# plaits_5u_rev2.net
KiCad netlist of a schematic drawn in EAGLE
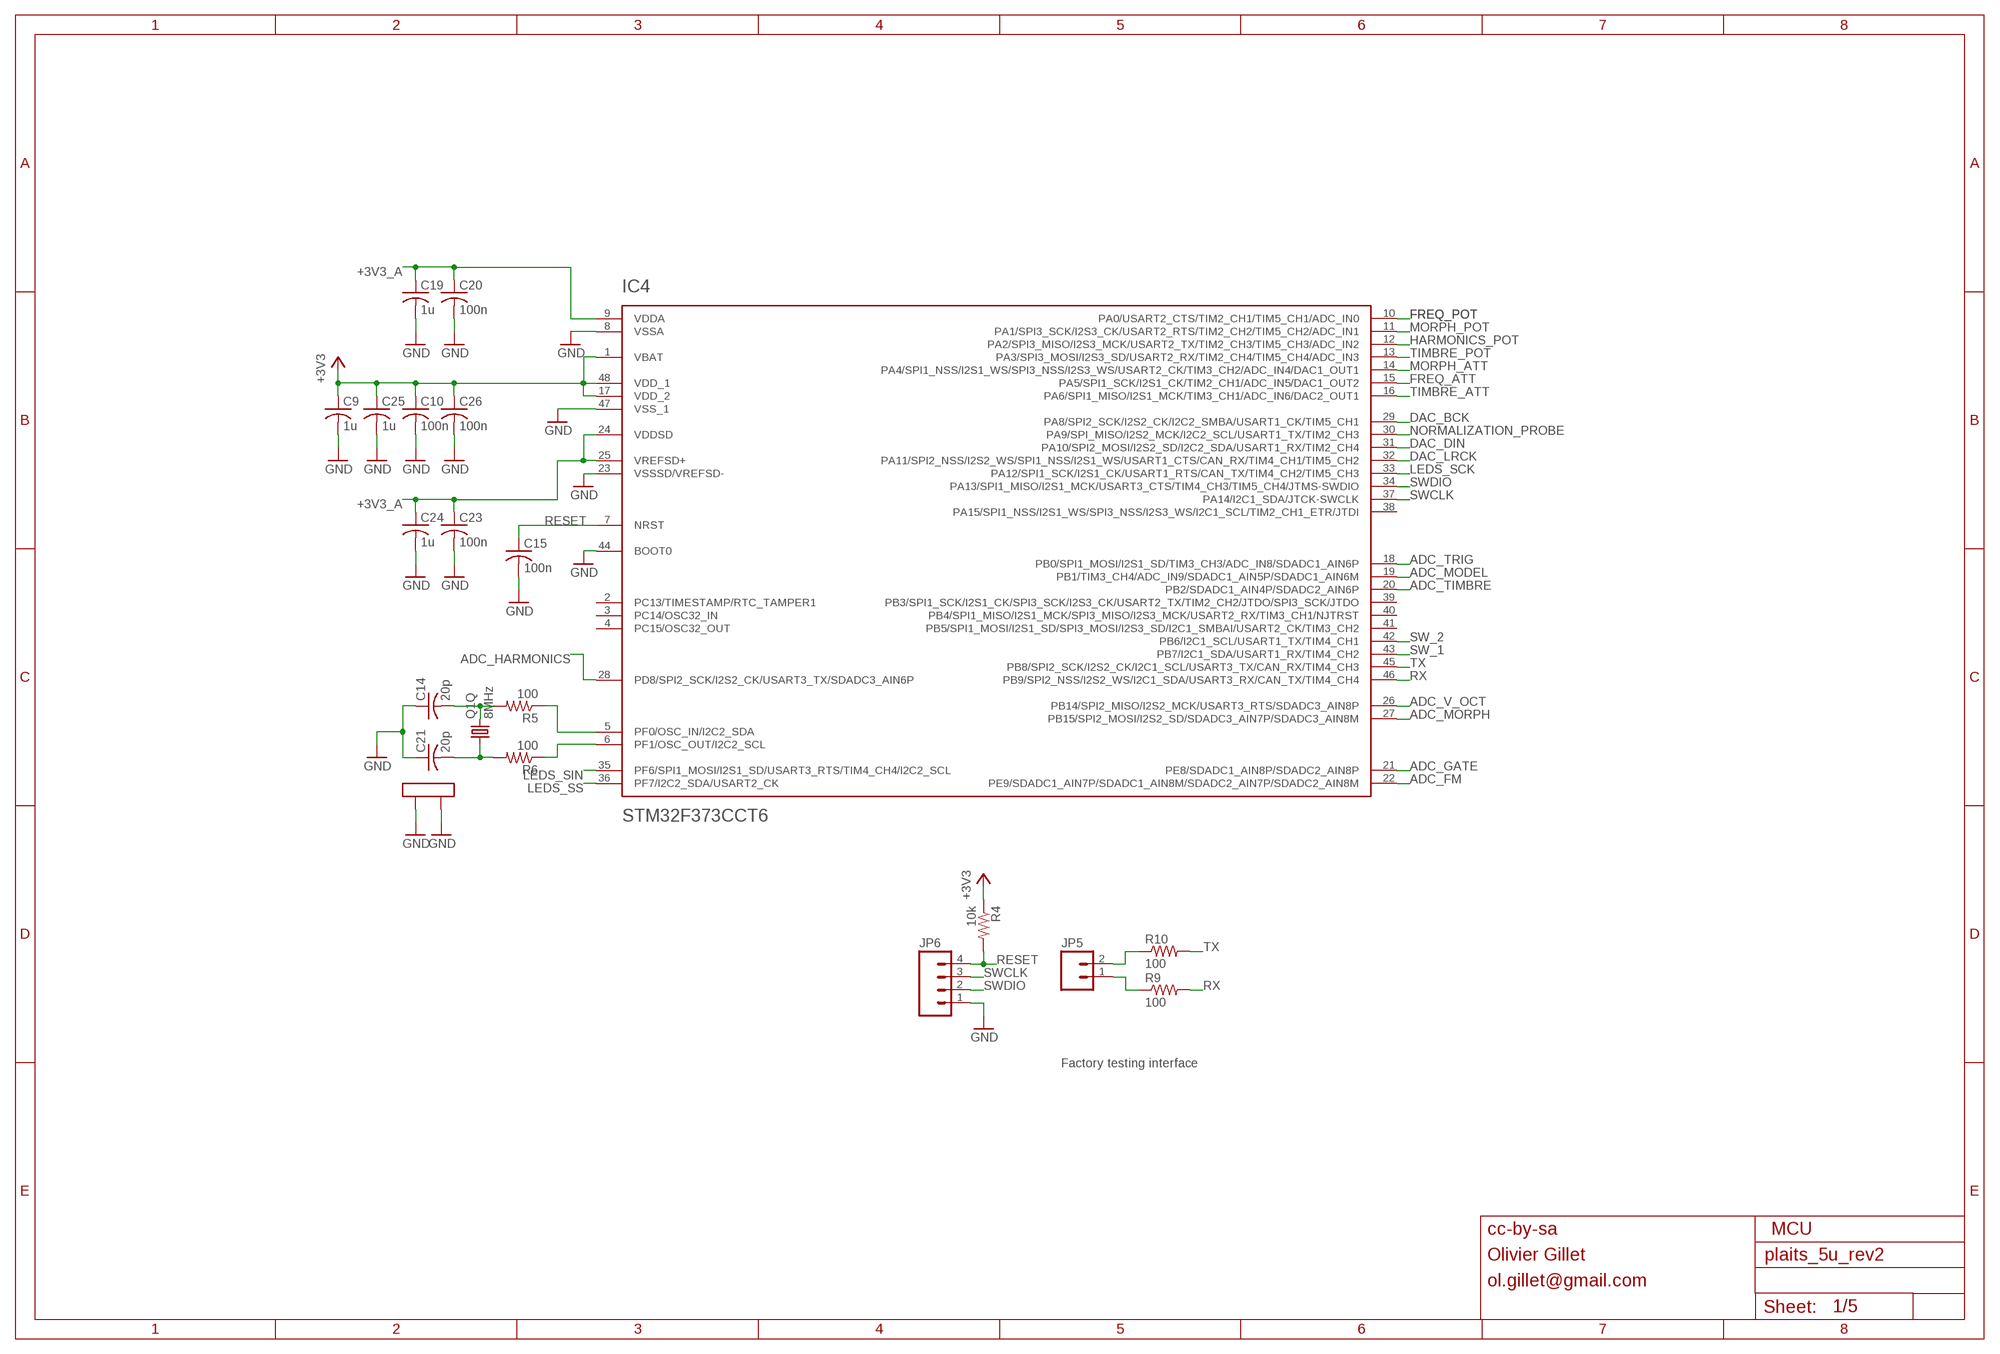
[diagram p0: schematic, sheet 1]
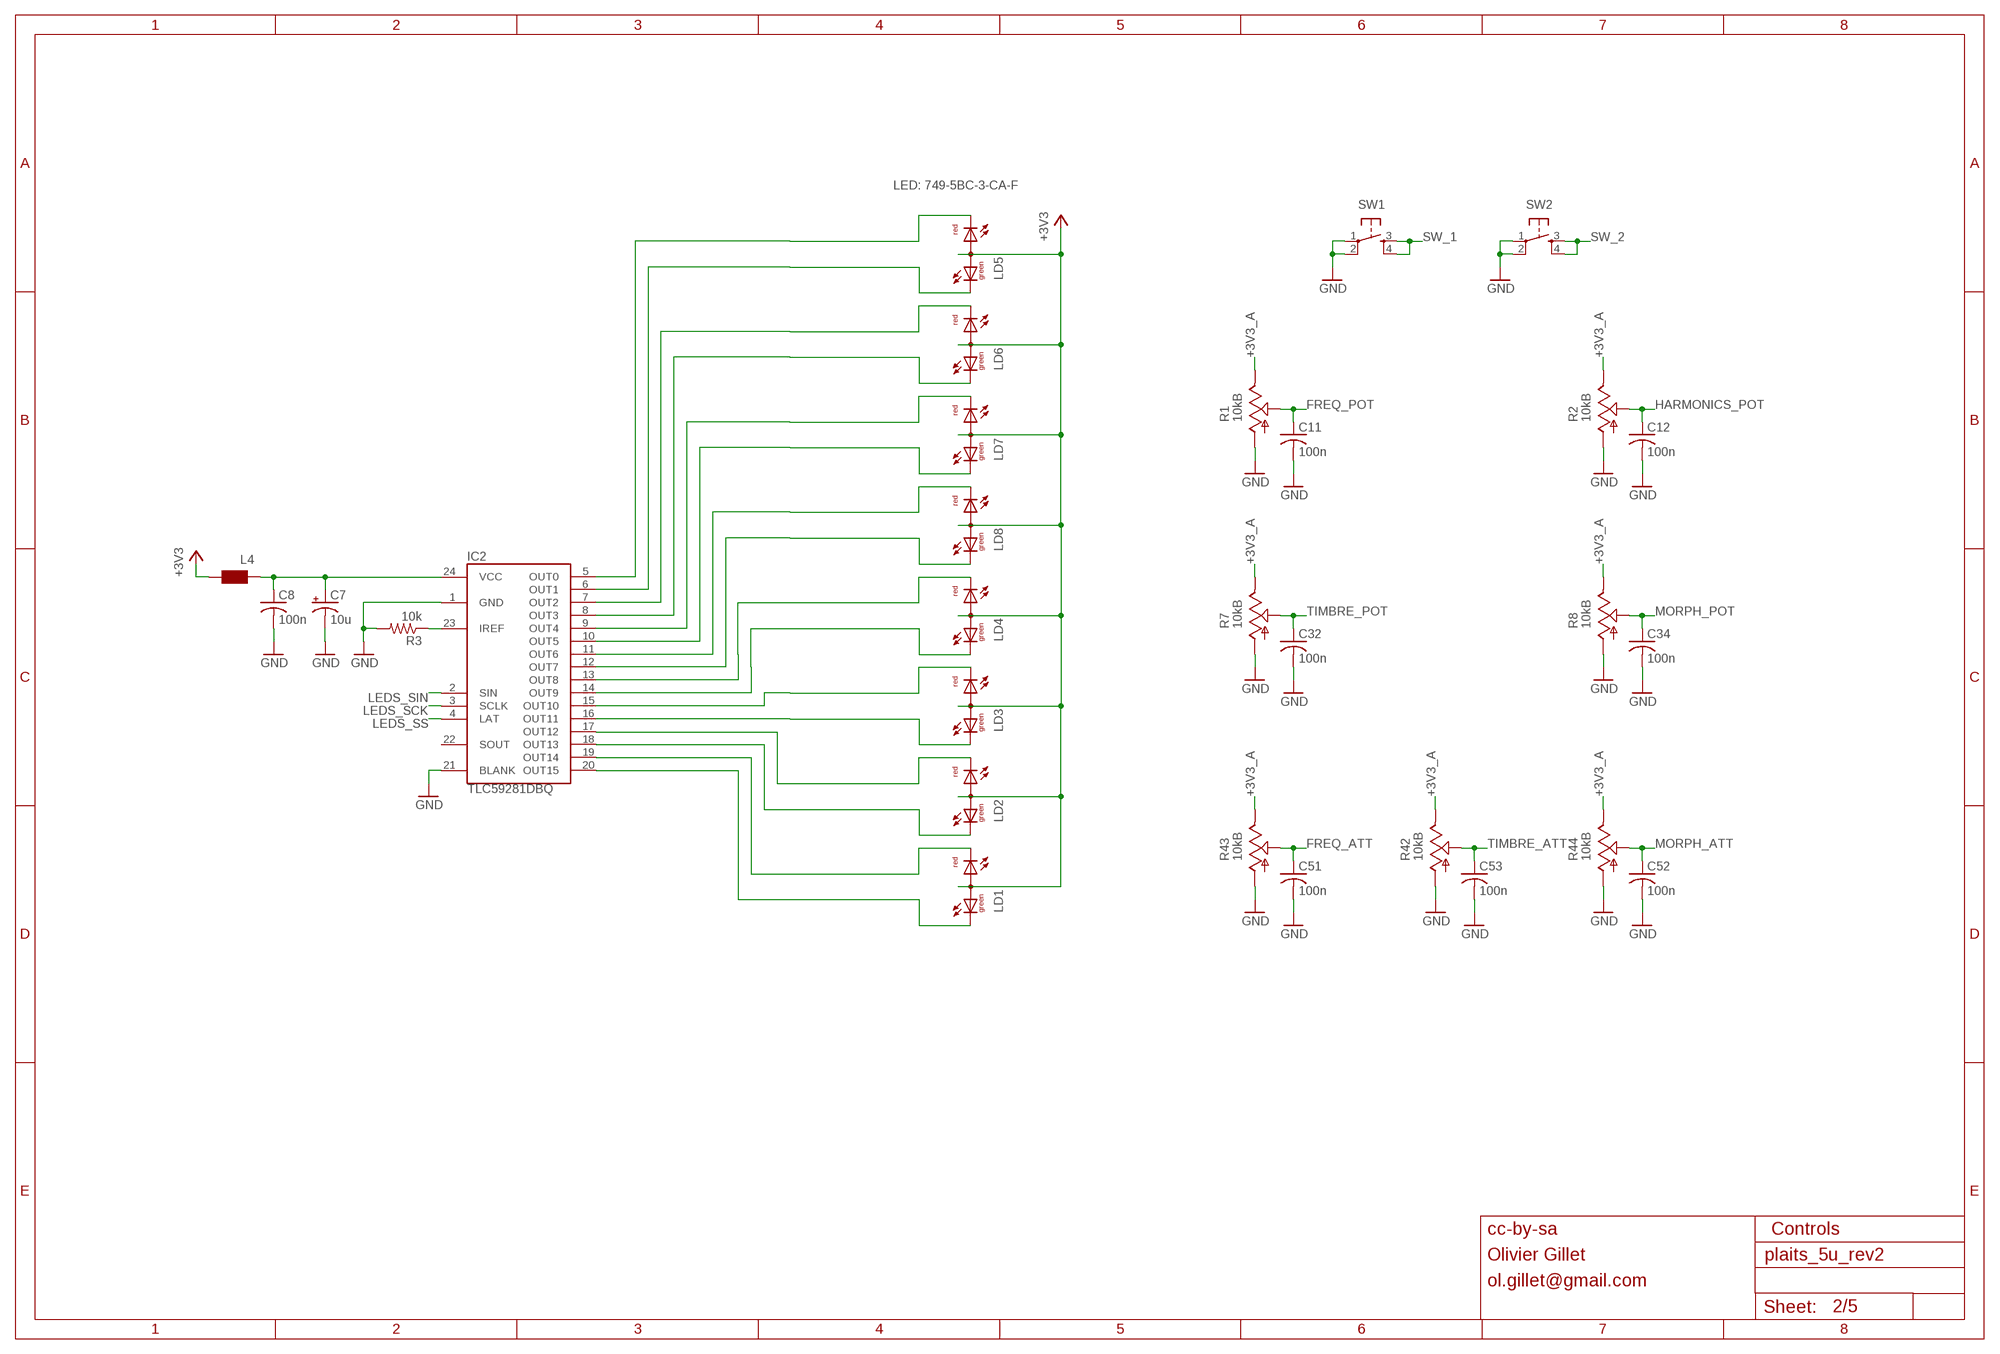
[diagram p1: schematic, sheet 2]
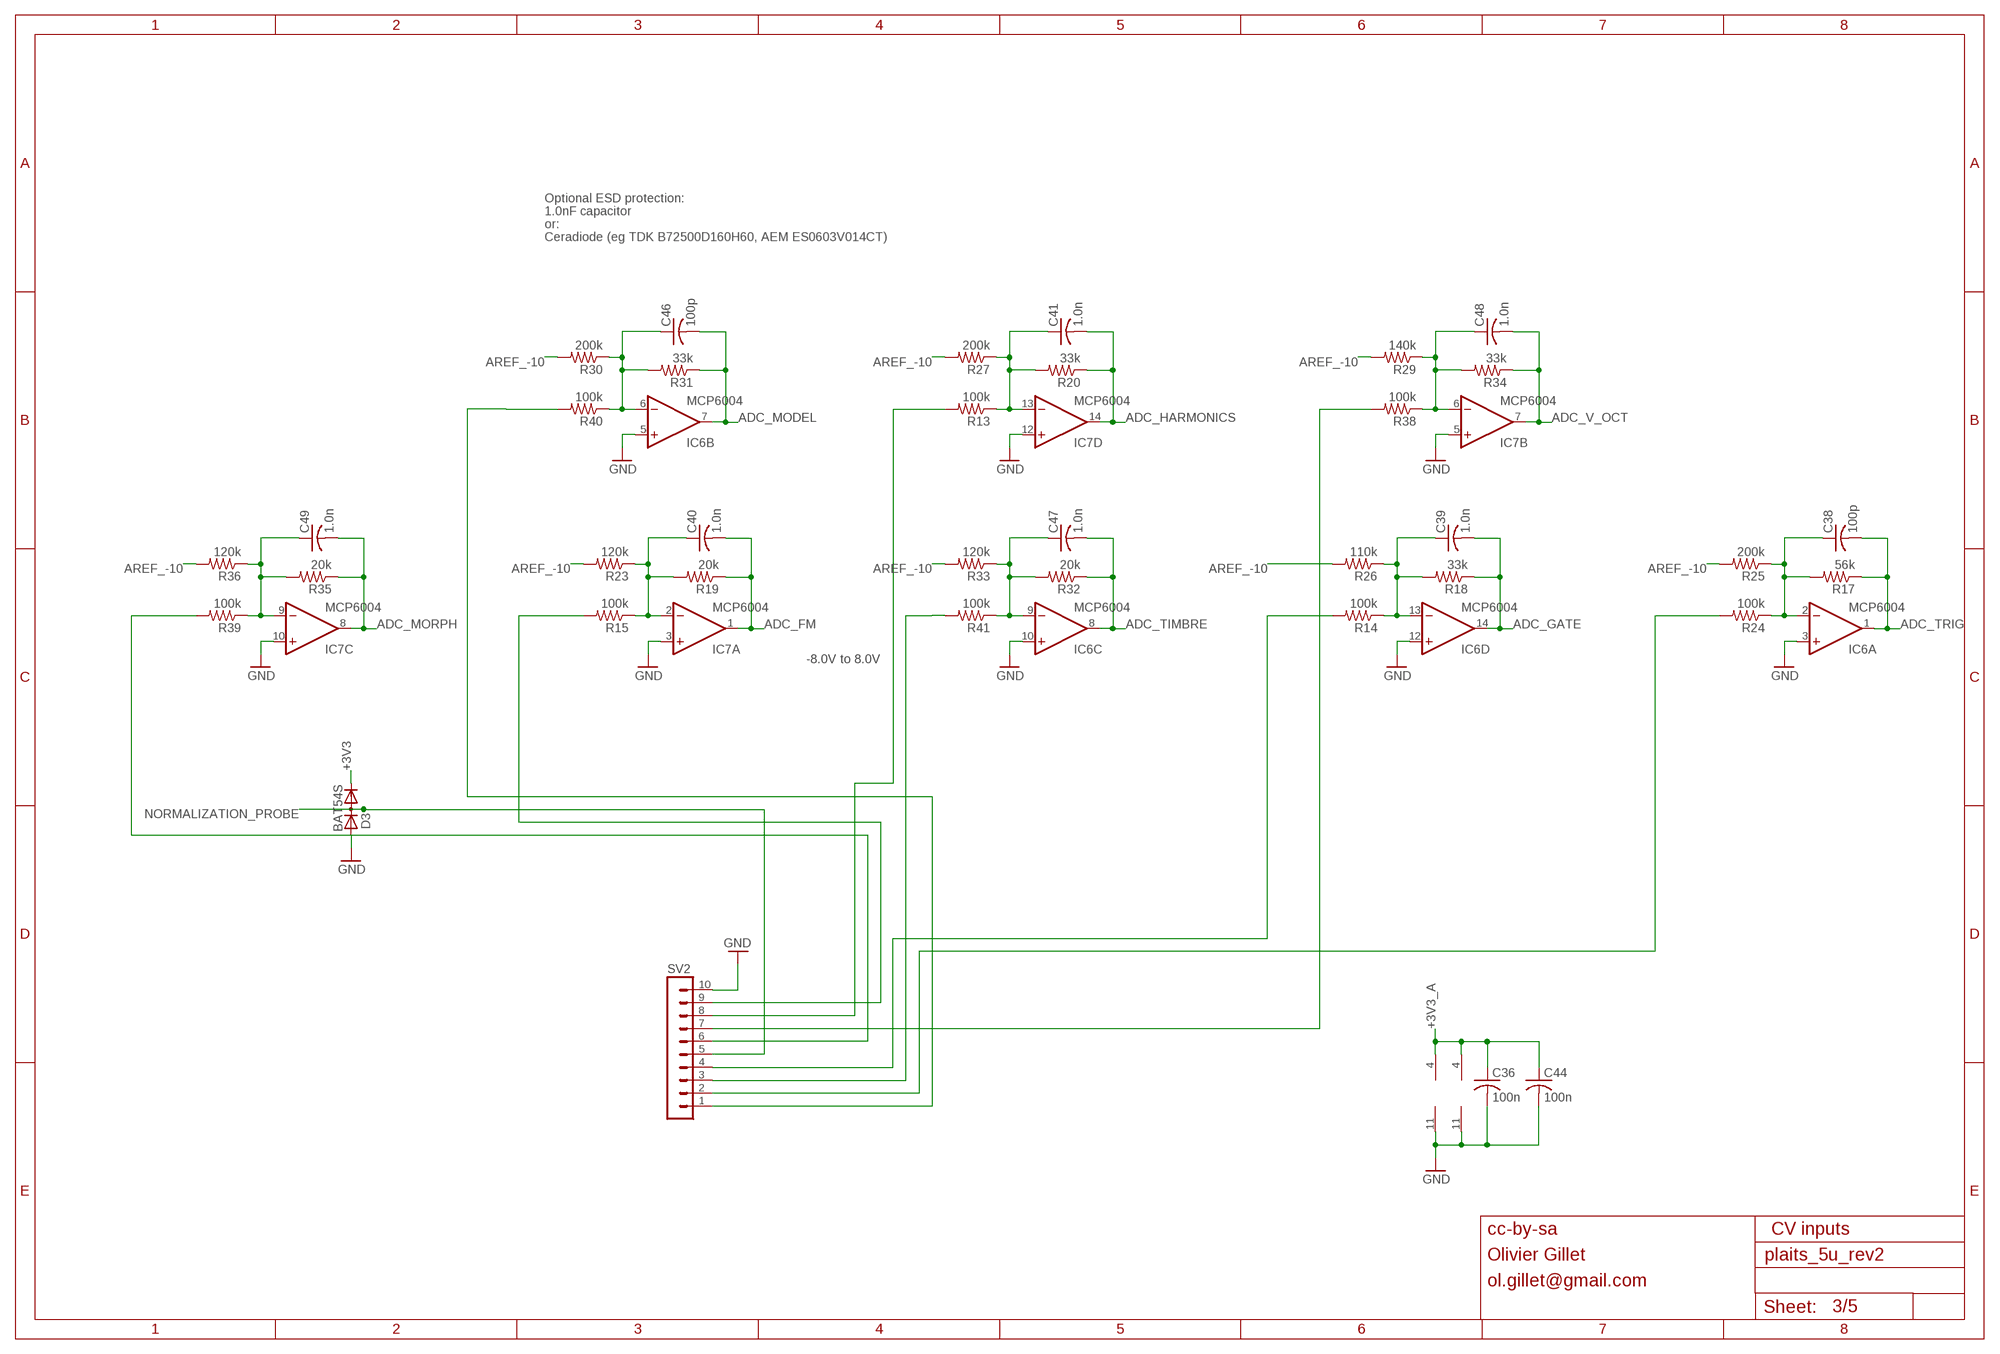
[diagram p2: schematic, sheet 3]
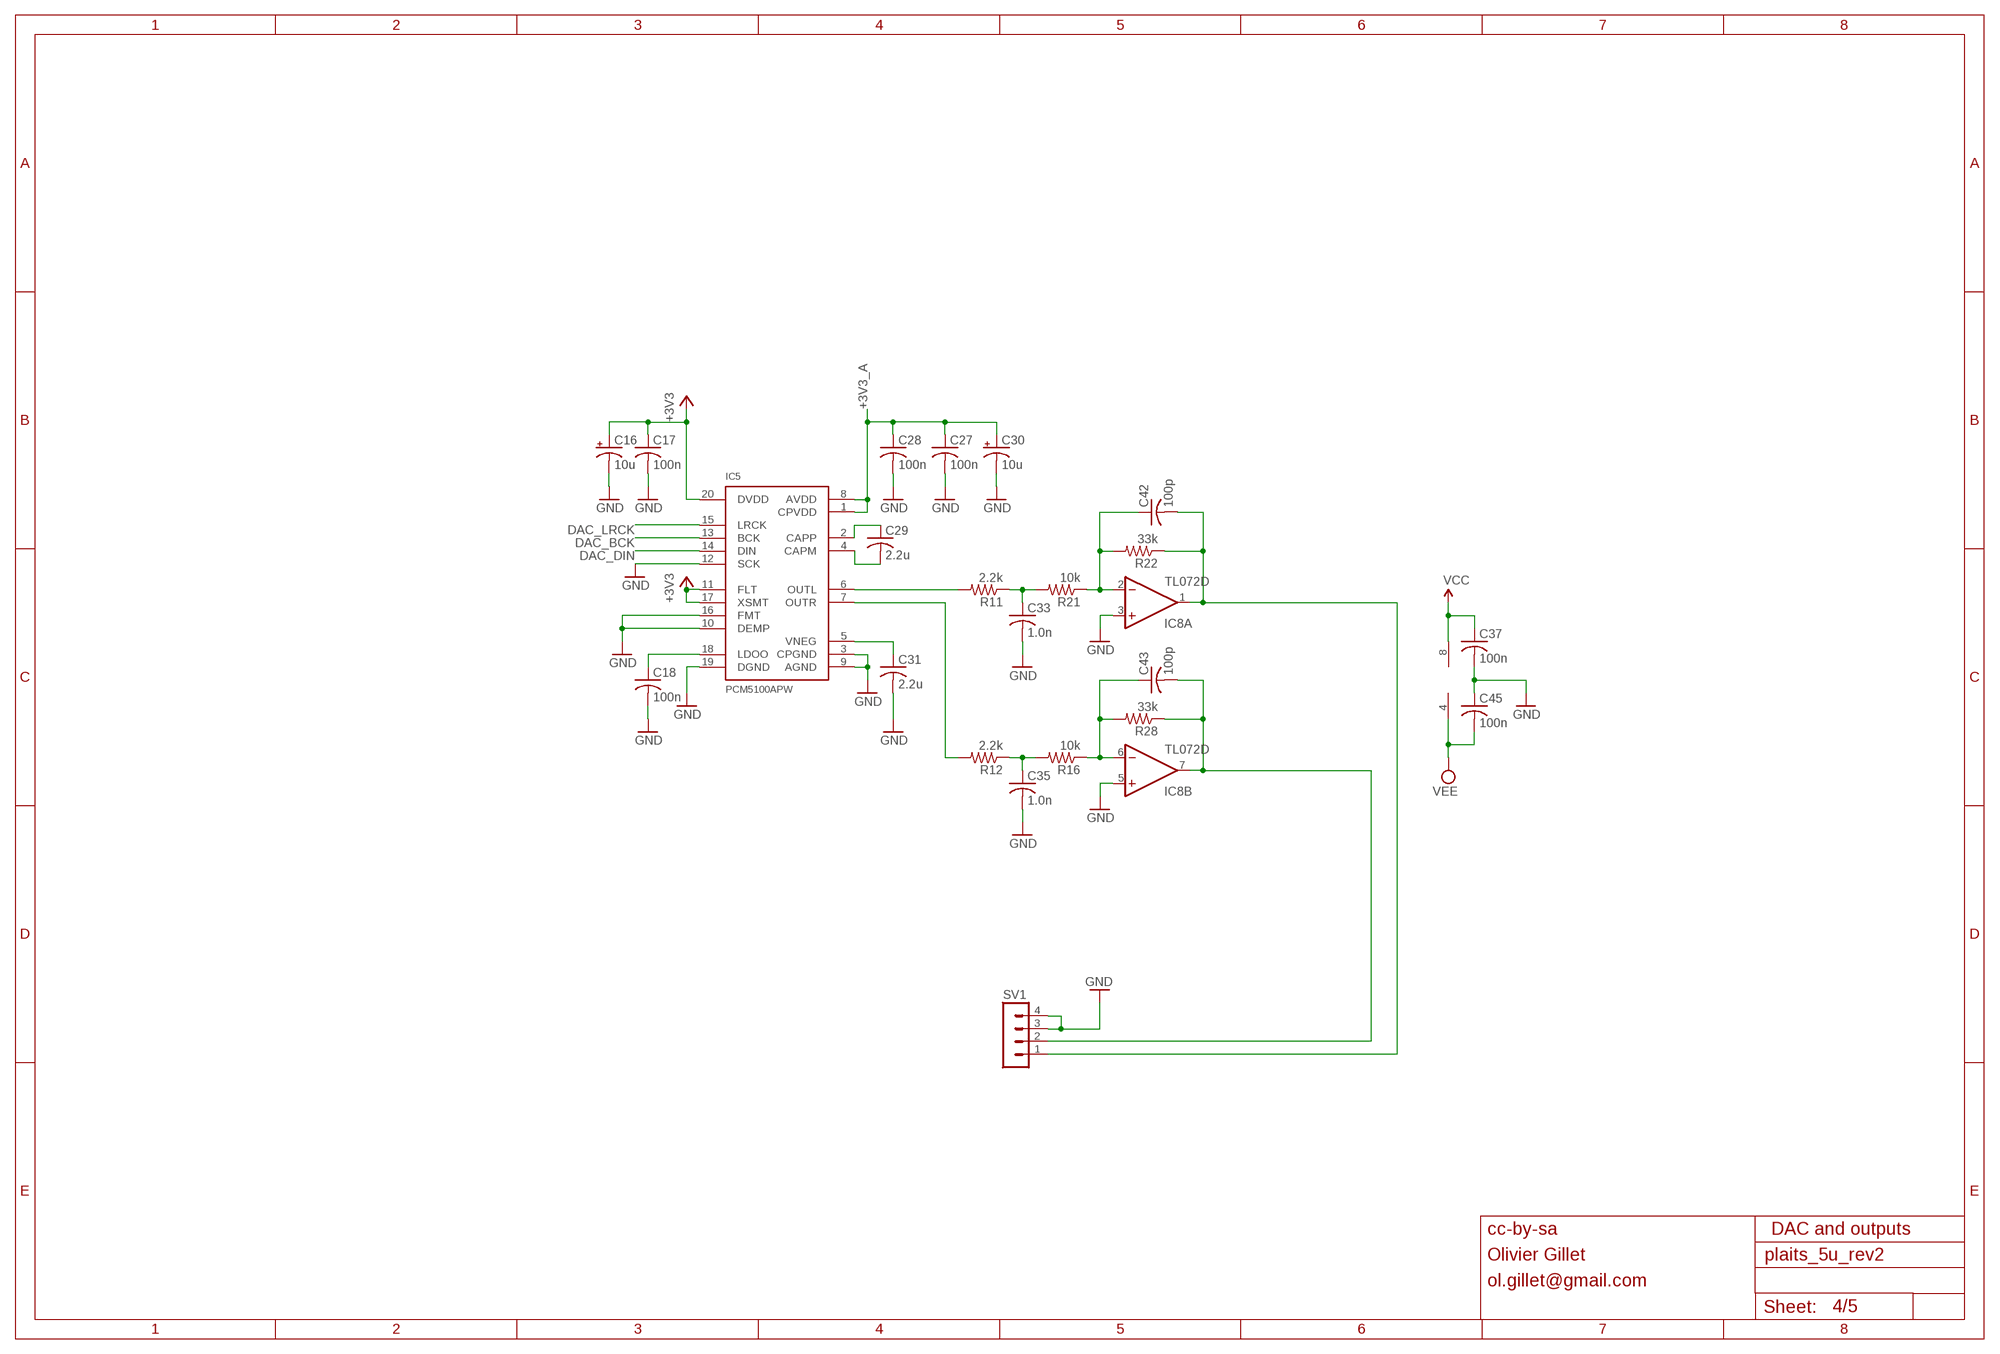
[diagram p3: schematic, sheet 4]
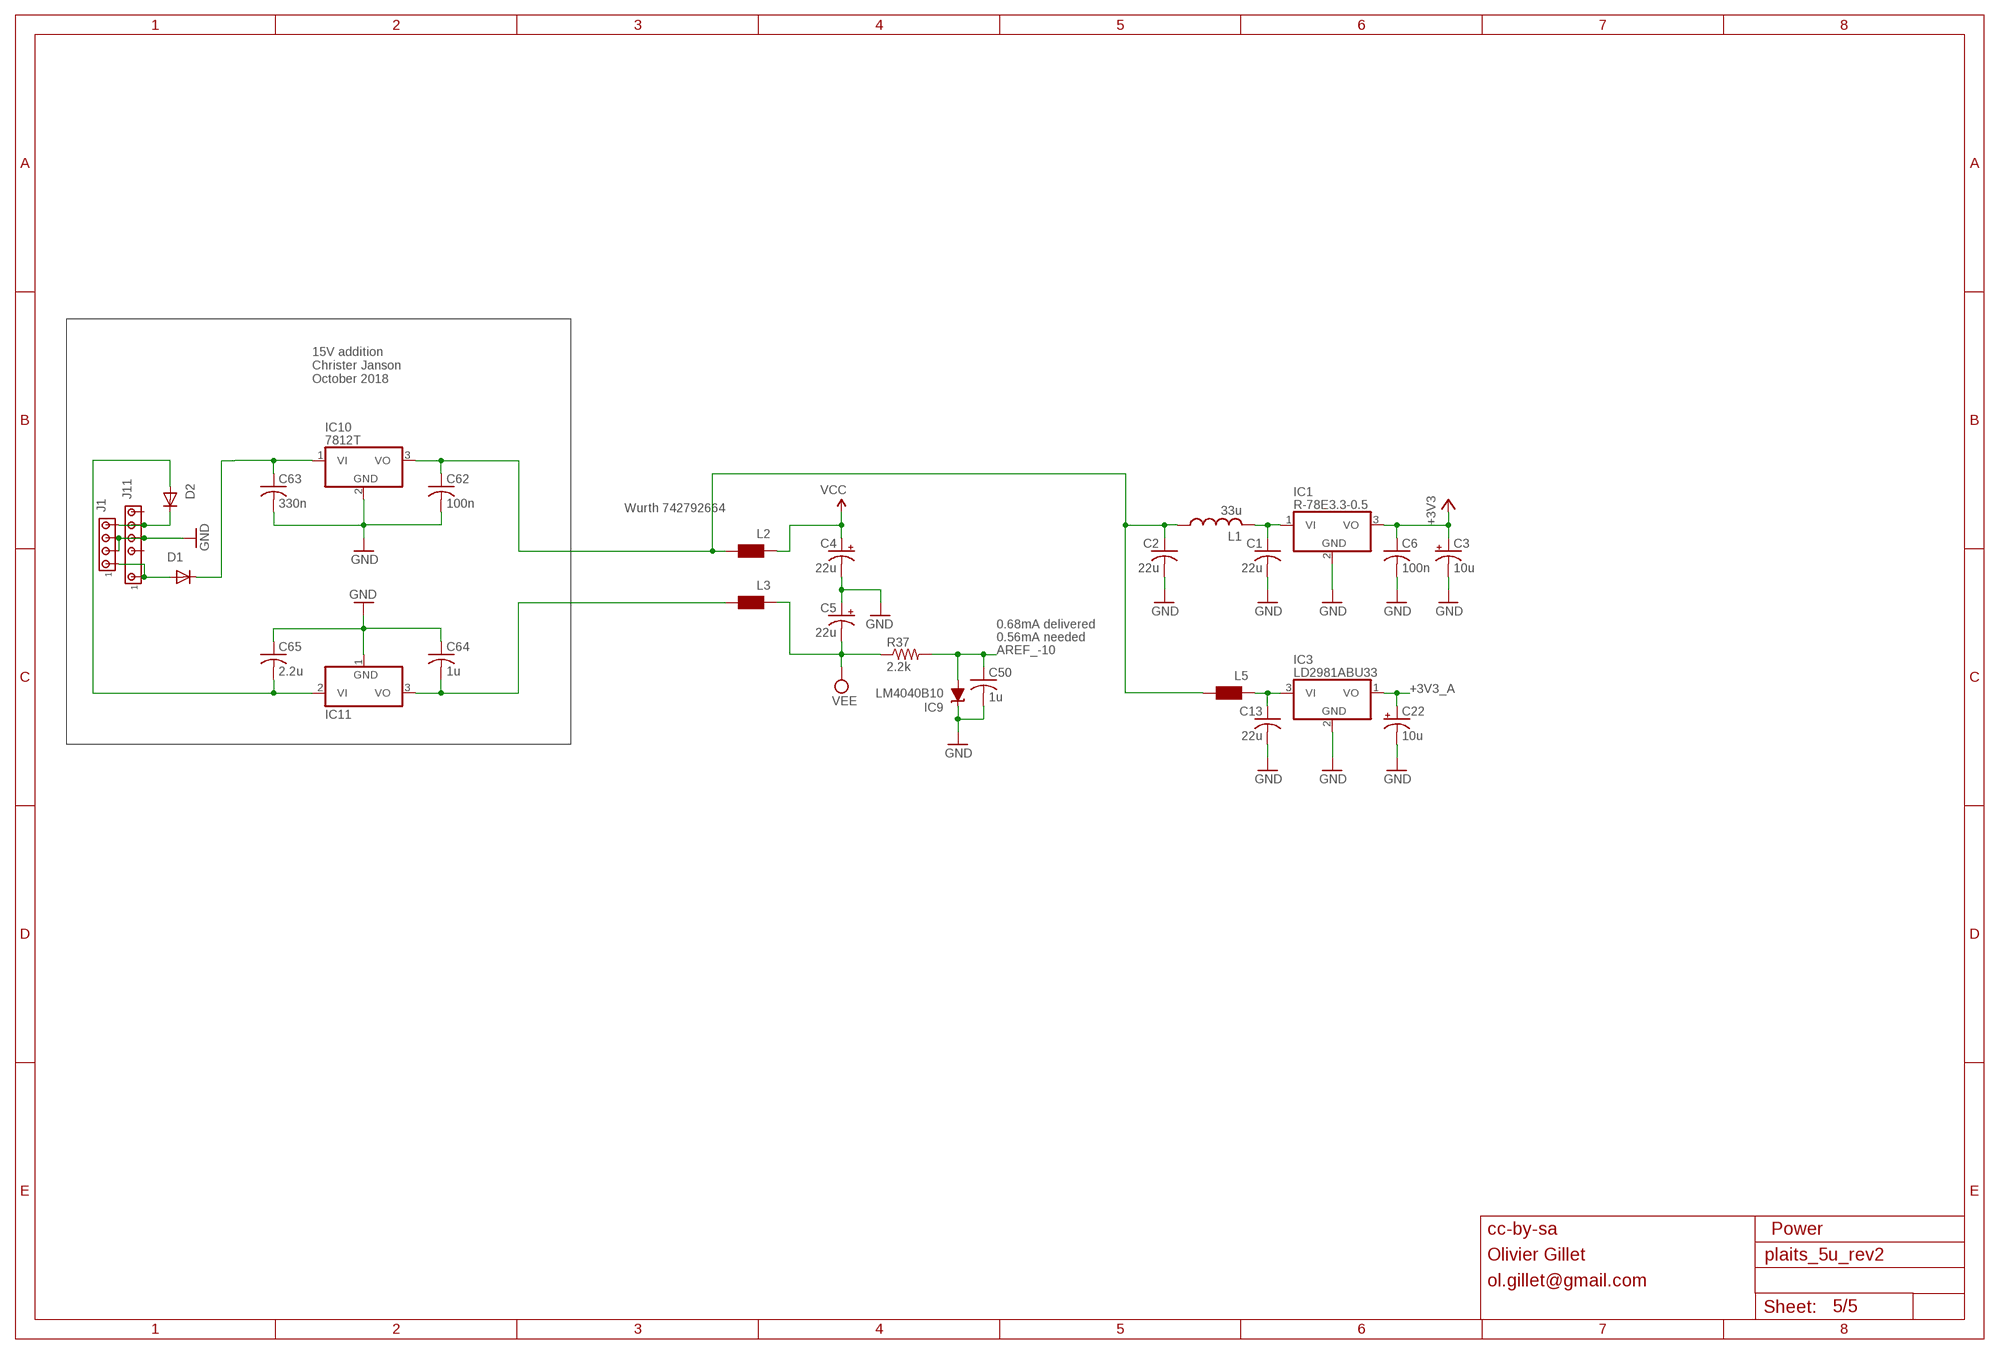
[diagram p4: schematic, sheet 5]

(export (version "E")
  (design (tool "Eeschema 10.0.6"))
  (components
    (comp (ref "C7")
      (value "10u")
      (footprint "eagle-import:PANASONIC_A")
      (libsource (lib "eagle-import") (part "CPOL-USA"))
    )
    (comp (ref "C8")
      (value "100n")
      (footprint "eagle-import:C0805")
      (libsource (lib "eagle-import") (part "C-USC0805"))
    )
    (comp (ref "C11")
      (value "100n")
      (footprint "eagle-import:C0805")
      (libsource (lib "eagle-import") (part "C-USC0805"))
    )
    (comp (ref "C12")
      (value "100n")
      (footprint "eagle-import:C0805")
      (libsource (lib "eagle-import") (part "C-USC0805"))
    )
    (comp (ref "C32")
      (value "100n")
      (footprint "eagle-import:C0805")
      (libsource (lib "eagle-import") (part "C-USC0805"))
    )
    (comp (ref "C34")
      (value "100n")
      (footprint "eagle-import:C0805")
      (libsource (lib "eagle-import") (part "C-USC0805"))
    )
    (comp (ref "C51")
      (value "100n")
      (footprint "eagle-import:C0805")
      (libsource (lib "eagle-import") (part "C-USC0805"))
    )
    (comp (ref "C52")
      (value "100n")
      (footprint "eagle-import:C0805")
      (libsource (lib "eagle-import") (part "C-USC0805"))
    )
    (comp (ref "C53")
      (value "100n")
      (footprint "eagle-import:C0805")
      (libsource (lib "eagle-import") (part "C-USC0805"))
    )
    (comp (ref "IC2")
      (value "TLC59281DBQ")
      (footprint "eagle-import:TSSOP24_0635")
      (libsource (lib "eagle-import") (part "TLC59281DBQ"))
    )
    (comp (ref "L4")
      (value "WE-CBF_0805")
      (footprint "eagle-import:0805")
      (libsource (lib "eagle-import") (part "WE-CBF_0805"))
    )
    (comp (ref "LD1")
      (value "DUOLED-RG-A")
      (footprint "eagle-import:DUOLED-A-5MM")
      (libsource (lib "eagle-import") (part "DUOLED-RG-A"))
    )
    (comp (ref "LD2")
      (value "DUOLED-RG-A")
      (footprint "eagle-import:DUOLED-A-5MM")
      (libsource (lib "eagle-import") (part "DUOLED-RG-A"))
    )
    (comp (ref "LD3")
      (value "DUOLED-RG-A")
      (footprint "eagle-import:DUOLED-A-5MM")
      (libsource (lib "eagle-import") (part "DUOLED-RG-A"))
    )
    (comp (ref "LD4")
      (value "DUOLED-RG-A")
      (footprint "eagle-import:DUOLED-A-5MM")
      (libsource (lib "eagle-import") (part "DUOLED-RG-A"))
    )
    (comp (ref "LD5")
      (value "DUOLED-RG-A")
      (footprint "eagle-import:DUOLED-A-5MM")
      (libsource (lib "eagle-import") (part "DUOLED-RG-A"))
    )
    (comp (ref "LD6")
      (value "DUOLED-RG-A")
      (footprint "eagle-import:DUOLED-A-5MM")
      (libsource (lib "eagle-import") (part "DUOLED-RG-A"))
    )
    (comp (ref "LD7")
      (value "DUOLED-RG-A")
      (footprint "eagle-import:DUOLED-A-5MM")
      (libsource (lib "eagle-import") (part "DUOLED-RG-A"))
    )
    (comp (ref "LD8")
      (value "DUOLED-RG-A")
      (footprint "eagle-import:DUOLED-A-5MM")
      (libsource (lib "eagle-import") (part "DUOLED-RG-A"))
    )
    (comp (ref "R1")
      (value "10kB")
      (footprint "eagle-import:ALPS_POT_VERTICAL_PS")
      (libsource (lib "eagle-import") (part "POT_USVERTICAL_PS"))
    )
    (comp (ref "R2")
      (value "10kB")
      (footprint "eagle-import:ALPS_POT_VERTICAL_PS")
      (libsource (lib "eagle-import") (part "POT_USVERTICAL_PS"))
    )
    (comp (ref "R3")
      (value "10k")
      (footprint "eagle-import:R0805")
      (libsource (lib "eagle-import") (part "R-US_R0805"))
    )
    (comp (ref "R7")
      (value "10kB")
      (footprint "eagle-import:ALPS_POT_VERTICAL_PS")
      (libsource (lib "eagle-import") (part "POT_USVERTICAL_PS"))
    )
    (comp (ref "R8")
      (value "10kB")
      (footprint "eagle-import:ALPS_POT_VERTICAL_PS")
      (libsource (lib "eagle-import") (part "POT_USVERTICAL_PS"))
    )
    (comp (ref "R42")
      (value "10kB")
      (footprint "eagle-import:ALPS_POT_VERTICAL")
      (libsource (lib "eagle-import") (part "POT_USVERTICAL"))
    )
    (comp (ref "R43")
      (value "10kB")
      (footprint "eagle-import:ALPS_POT_VERTICAL")
      (libsource (lib "eagle-import") (part "POT_USVERTICAL"))
    )
    (comp (ref "R44")
      (value "10kB")
      (footprint "eagle-import:ALPS_POT_VERTICAL")
      (libsource (lib "eagle-import") (part "POT_USVERTICAL"))
    )
    (comp (ref "SW1")
      (value "TAC_SWITCHPTH")
      (footprint "eagle-import:TACTILE-PTH")
      (libsource (lib "eagle-import") (part "TAC_SWITCHPTH"))
    )
    (comp (ref "SW2")
      (value "TAC_SWITCHPTH")
      (footprint "eagle-import:TACTILE-PTH")
      (libsource (lib "eagle-import") (part "TAC_SWITCHPTH"))
    )
    (comp (ref "C36")
      (value "100n")
      (footprint "eagle-import:C0805")
      (libsource (lib "eagle-import") (part "C-USC0805"))
    )
    (comp (ref "C38")
      (value "100p")
      (footprint "eagle-import:C0805")
      (libsource (lib "eagle-import") (part "C-USC0805"))
    )
    (comp (ref "C39")
      (value "1.0n")
      (footprint "eagle-import:C0805")
      (libsource (lib "eagle-import") (part "C-USC0805"))
    )
    (comp (ref "C40")
      (value "1.0n")
      (footprint "eagle-import:C0805")
      (libsource (lib "eagle-import") (part "C-USC0805"))
    )
    (comp (ref "C41")
      (value "1.0n")
      (footprint "eagle-import:C0805")
      (libsource (lib "eagle-import") (part "C-USC0805"))
    )
    (comp (ref "C44")
      (value "100n")
      (footprint "eagle-import:C0805")
      (libsource (lib "eagle-import") (part "C-USC0805"))
    )
    (comp (ref "C46")
      (value "100p")
      (footprint "eagle-import:C0805")
      (libsource (lib "eagle-import") (part "C-USC0805"))
    )
    (comp (ref "C47")
      (value "1.0n")
      (footprint "eagle-import:C0805")
      (libsource (lib "eagle-import") (part "C-USC0805"))
    )
    (comp (ref "C48")
      (value "1.0n")
      (footprint "eagle-import:C0805")
      (libsource (lib "eagle-import") (part "C-USC0805"))
    )
    (comp (ref "C49")
      (value "1.0n")
      (footprint "eagle-import:C0805")
      (libsource (lib "eagle-import") (part "C-USC0805"))
    )
    (comp (ref "D3")
      (value "BAT54S")
      (footprint "eagle-import:SOT23")
      (libsource (lib "eagle-import") (part "DIODE_2CACA-SOT23"))
    )
    (comp (ref "IC6")
      (value "MCP6004")
      (footprint "eagle-import:SO14")
      (libsource (lib "eagle-import") (part "TL074D"))
    )
    (comp (ref "IC7")
      (value "MCP6004")
      (footprint "eagle-import:SO14")
      (libsource (lib "eagle-import") (part "TL074D"))
    )
    (comp (ref "R13")
      (value "100k")
      (footprint "eagle-import:R0805")
      (libsource (lib "eagle-import") (part "R-US_R0805"))
    )
    (comp (ref "R14")
      (value "100k")
      (footprint "eagle-import:R0805")
      (libsource (lib "eagle-import") (part "R-US_R0805"))
    )
    (comp (ref "R15")
      (value "100k")
      (footprint "eagle-import:R0805")
      (libsource (lib "eagle-import") (part "R-US_R0805"))
    )
    (comp (ref "R17")
      (value "56k")
      (footprint "eagle-import:R0805")
      (libsource (lib "eagle-import") (part "R-US_R0805"))
    )
    (comp (ref "R18")
      (value "33k")
      (footprint "eagle-import:R0805")
      (libsource (lib "eagle-import") (part "R-US_R0805"))
    )
    (comp (ref "R19")
      (value "20k")
      (footprint "eagle-import:R0805")
      (libsource (lib "eagle-import") (part "R-US_R0805"))
    )
    (comp (ref "R20")
      (value "33k")
      (footprint "eagle-import:R0805")
      (libsource (lib "eagle-import") (part "R-US_R0805"))
    )
    (comp (ref "R23")
      (value "120k")
      (footprint "eagle-import:R0805")
      (libsource (lib "eagle-import") (part "R-US_R0805"))
    )
    (comp (ref "R24")
      (value "100k")
      (footprint "eagle-import:R0805")
      (libsource (lib "eagle-import") (part "R-US_R0805"))
    )
    (comp (ref "R25")
      (value "200k")
      (footprint "eagle-import:R0805")
      (libsource (lib "eagle-import") (part "R-US_R0805"))
    )
    (comp (ref "R26")
      (value "110k")
      (footprint "eagle-import:R0805")
      (libsource (lib "eagle-import") (part "R-US_R0805"))
    )
    (comp (ref "R27")
      (value "200k")
      (footprint "eagle-import:R0805")
      (libsource (lib "eagle-import") (part "R-US_R0805"))
    )
    (comp (ref "R29")
      (value "140k")
      (footprint "eagle-import:R0805")
      (libsource (lib "eagle-import") (part "R-US_R0805"))
    )
    (comp (ref "R30")
      (value "200k")
      (footprint "eagle-import:R0805")
      (libsource (lib "eagle-import") (part "R-US_R0805"))
    )
    (comp (ref "R31")
      (value "33k")
      (footprint "eagle-import:R0805")
      (libsource (lib "eagle-import") (part "R-US_R0805"))
    )
    (comp (ref "R32")
      (value "20k")
      (footprint "eagle-import:R0805")
      (libsource (lib "eagle-import") (part "R-US_R0805"))
    )
    (comp (ref "R33")
      (value "120k")
      (footprint "eagle-import:R0805")
      (libsource (lib "eagle-import") (part "R-US_R0805"))
    )
    (comp (ref "R34")
      (value "33k")
      (footprint "eagle-import:R0805")
      (libsource (lib "eagle-import") (part "R-US_R0805"))
    )
    (comp (ref "R35")
      (value "20k")
      (footprint "eagle-import:R0805")
      (libsource (lib "eagle-import") (part "R-US_R0805"))
    )
    (comp (ref "R36")
      (value "120k")
      (footprint "eagle-import:R0805")
      (libsource (lib "eagle-import") (part "R-US_R0805"))
    )
    (comp (ref "R38")
      (value "100k")
      (footprint "eagle-import:R0805")
      (libsource (lib "eagle-import") (part "R-US_R0805"))
    )
    (comp (ref "R39")
      (value "100k")
      (footprint "eagle-import:R0805")
      (libsource (lib "eagle-import") (part "R-US_R0805"))
    )
    (comp (ref "R40")
      (value "100k")
      (footprint "eagle-import:R0805")
      (libsource (lib "eagle-import") (part "R-US_R0805"))
    )
    (comp (ref "R41")
      (value "100k")
      (footprint "eagle-import:R0805")
      (libsource (lib "eagle-import") (part "R-US_R0805"))
    )
    (comp (ref "SV2")
      (value "MA10-1")
      (footprint "eagle-import:MA10-1")
      (libsource (lib "eagle-import") (part "MA10-1"))
    )
    (comp (ref "C9")
      (value "1u")
      (footprint "eagle-import:C0805")
      (libsource (lib "eagle-import") (part "C-USC0805"))
    )
    (comp (ref "C10")
      (value "100n")
      (footprint "eagle-import:C0805")
      (libsource (lib "eagle-import") (part "C-USC0805"))
    )
    (comp (ref "C14")
      (value "20p")
      (footprint "eagle-import:C0805")
      (libsource (lib "eagle-import") (part "C-USC0805"))
    )
    (comp (ref "C15")
      (value "100n")
      (footprint "eagle-import:C0805")
      (libsource (lib "eagle-import") (part "C-USC0805"))
    )
    (comp (ref "C19")
      (value "1u")
      (footprint "eagle-import:C0805")
      (libsource (lib "eagle-import") (part "C-USC0805"))
    )
    (comp (ref "C20")
      (value "100n")
      (footprint "eagle-import:C0805")
      (libsource (lib "eagle-import") (part "C-USC0805"))
    )
    (comp (ref "C21")
      (value "20p")
      (footprint "eagle-import:C0805")
      (libsource (lib "eagle-import") (part "C-USC0805"))
    )
    (comp (ref "C23")
      (value "100n")
      (footprint "eagle-import:C0805")
      (libsource (lib "eagle-import") (part "C-USC0805"))
    )
    (comp (ref "C24")
      (value "1u")
      (footprint "eagle-import:C0805")
      (libsource (lib "eagle-import") (part "C-USC0805"))
    )
    (comp (ref "C25")
      (value "1u")
      (footprint "eagle-import:C0805")
      (libsource (lib "eagle-import") (part "C-USC0805"))
    )
    (comp (ref "C26")
      (value "100n")
      (footprint "eagle-import:C0805")
      (libsource (lib "eagle-import") (part "C-USC0805"))
    )
    (comp (ref "IC4")
      (value "STM32F373CCT6")
      (footprint "eagle-import:LQFP48")
      (libsource (lib "eagle-import") (part "STM32F373C"))
    )
    (comp (ref "JP5")
      (value "M02PTH")
      (footprint "eagle-import:1X02")
      (libsource (lib "eagle-import") (part "M02PTH"))
    )
    (comp (ref "JP6")
      (value "M04PTH")
      (footprint "eagle-import:1X04")
      (libsource (lib "eagle-import") (part "M04PTH"))
    )
    (comp (ref "Q1")
      (value "8MHz")
      (footprint "eagle-import:CTS406")
      (libsource (lib "eagle-import") (part "CRYSTAL"))
    )
    (comp (ref "R4")
      (value "10k")
      (footprint "eagle-import:R0805")
      (libsource (lib "eagle-import") (part "R-US_R0805"))
    )
    (comp (ref "R5")
      (value "100")
      (footprint "eagle-import:R0805")
      (libsource (lib "eagle-import") (part "R-US_R0805"))
    )
    (comp (ref "R6")
      (value "100")
      (footprint "eagle-import:R0805")
      (libsource (lib "eagle-import") (part "R-US_R0805"))
    )
    (comp (ref "R9")
      (value "100")
      (footprint "eagle-import:R0805")
      (libsource (lib "eagle-import") (part "R-US_R0805"))
    )
    (comp (ref "R10")
      (value "100")
      (footprint "eagle-import:R0805")
      (libsource (lib "eagle-import") (part "R-US_R0805"))
    )
    (comp (ref "C16")
      (value "10u")
      (footprint "eagle-import:PANASONIC_A")
      (libsource (lib "eagle-import") (part "CPOL-USA"))
    )
    (comp (ref "C17")
      (value "100n")
      (footprint "eagle-import:C0805")
      (libsource (lib "eagle-import") (part "C-USC0805"))
    )
    (comp (ref "C18")
      (value "100n")
      (footprint "eagle-import:C0805")
      (libsource (lib "eagle-import") (part "C-USC0805"))
    )
    (comp (ref "C27")
      (value "100n")
      (footprint "eagle-import:C0805")
      (libsource (lib "eagle-import") (part "C-USC0805"))
    )
    (comp (ref "C28")
      (value "100n")
      (footprint "eagle-import:C0805")
      (libsource (lib "eagle-import") (part "C-USC0805"))
    )
    (comp (ref "C29")
      (value "2.2u")
      (footprint "eagle-import:C0805")
      (libsource (lib "eagle-import") (part "C-USC0805"))
    )
    (comp (ref "C30")
      (value "10u")
      (footprint "eagle-import:PANASONIC_A")
      (libsource (lib "eagle-import") (part "CPOL-USA"))
    )
    (comp (ref "C31")
      (value "2.2u")
      (footprint "eagle-import:C0805")
      (libsource (lib "eagle-import") (part "C-USC0805"))
    )
    (comp (ref "C33")
      (value "1.0n")
      (footprint "eagle-import:C0805")
      (libsource (lib "eagle-import") (part "C-USC0805"))
    )
    (comp (ref "C35")
      (value "1.0n")
      (footprint "eagle-import:C0805")
      (libsource (lib "eagle-import") (part "C-USC0805"))
    )
    (comp (ref "C37")
      (value "100n")
      (footprint "eagle-import:C0805")
      (libsource (lib "eagle-import") (part "C-USC0805"))
    )
    (comp (ref "C42")
      (value "100p")
      (footprint "eagle-import:C0805")
      (libsource (lib "eagle-import") (part "C-USC0805"))
    )
    (comp (ref "C43")
      (value "100p")
      (footprint "eagle-import:C0805")
      (libsource (lib "eagle-import") (part "C-USC0805"))
    )
    (comp (ref "C45")
      (value "100n")
      (footprint "eagle-import:C0805")
      (libsource (lib "eagle-import") (part "C-USC0805"))
    )
    (comp (ref "IC5")
      (value "PCM5100APW")
      (footprint "eagle-import:SSOP20")
      (libsource (lib "eagle-import") (part "PCM5100PW"))
    )
    (comp (ref "IC8")
      (value "TL072D")
      (footprint "eagle-import:SO08")
      (libsource (lib "eagle-import") (part "TL072D"))
    )
    (comp (ref "R11")
      (value "2.2k")
      (footprint "eagle-import:R0805")
      (libsource (lib "eagle-import") (part "R-US_R0805"))
    )
    (comp (ref "R12")
      (value "2.2k")
      (footprint "eagle-import:R0805")
      (libsource (lib "eagle-import") (part "R-US_R0805"))
    )
    (comp (ref "R16")
      (value "10k")
      (footprint "eagle-import:R0805")
      (libsource (lib "eagle-import") (part "R-US_R0805"))
    )
    (comp (ref "R21")
      (value "10k")
      (footprint "eagle-import:R0805")
      (libsource (lib "eagle-import") (part "R-US_R0805"))
    )
    (comp (ref "R22")
      (value "33k")
      (footprint "eagle-import:R0805")
      (libsource (lib "eagle-import") (part "R-US_R0805"))
    )
    (comp (ref "R28")
      (value "33k")
      (footprint "eagle-import:R0805")
      (libsource (lib "eagle-import") (part "R-US_R0805"))
    )
    (comp (ref "SV1")
      (value "MA04-1")
      (footprint "eagle-import:MA04-1")
      (libsource (lib "eagle-import") (part "MA04-1"))
    )
    (comp (ref "C1")
      (value "22u")
      (footprint "eagle-import:C1206")
      (libsource (lib "eagle-import") (part "C-USC1206"))
    )
    (comp (ref "C2")
      (value "22u")
      (footprint "eagle-import:C1206")
      (libsource (lib "eagle-import") (part "C-USC1206"))
    )
    (comp (ref "C3")
      (value "10u")
      (footprint "eagle-import:PANASONIC_A")
      (libsource (lib "eagle-import") (part "CPOL-USA"))
    )
    (comp (ref "C4")
      (value "22u")
      (footprint "eagle-import:PANASONIC_B")
      (libsource (lib "eagle-import") (part "CPOL-USB"))
    )
    (comp (ref "C5")
      (value "22u")
      (footprint "eagle-import:PANASONIC_B")
      (libsource (lib "eagle-import") (part "CPOL-USB"))
    )
    (comp (ref "C6")
      (value "100n")
      (footprint "eagle-import:C0805")
      (libsource (lib "eagle-import") (part "C-USC0805"))
    )
    (comp (ref "C13")
      (value "22u")
      (footprint "eagle-import:C1206")
      (libsource (lib "eagle-import") (part "C-USC1206"))
    )
    (comp (ref "C22")
      (value "10u")
      (footprint "eagle-import:PANASONIC_A")
      (libsource (lib "eagle-import") (part "CPOL-USA"))
    )
    (comp (ref "C50")
      (value "1u")
      (footprint "eagle-import:C0805")
      (libsource (lib "eagle-import") (part "C-USC0805"))
    )
    (comp (ref "C62")
      (value "100n")
      (footprint "eagle-import:C0805")
      (libsource (lib "eagle-import") (part "C-USC0805"))
    )
    (comp (ref "C63")
      (value "330n")
      (footprint "eagle-import:C0805")
      (libsource (lib "eagle-import") (part "C-USC0805"))
    )
    (comp (ref "C64")
      (value "1u")
      (footprint "eagle-import:C0805")
      (libsource (lib "eagle-import") (part "C-USC0805"))
    )
    (comp (ref "C65")
      (value "2.2u")
      (footprint "eagle-import:C0805")
      (libsource (lib "eagle-import") (part "C-USC0805"))
    )
    (comp (ref "D1")
      (value "1N5819HW")
      (footprint "eagle-import:SOD123")
      (libsource (lib "eagle-import") (part "DIODE-SOD123"))
    )
    (comp (ref "D2")
      (value "1N5819HW")
      (footprint "eagle-import:SOD123")
      (libsource (lib "eagle-import") (part "DIODE-SOD123"))
    )
    (comp (ref "IC1")
      (value "R-78E3.3-0.5")
      (footprint "eagle-import:WE78")
      (libsource (lib "eagle-import") (part "WE173950378"))
    )
    (comp (ref "IC3")
      (value "LD2981ABU33")
      (footprint "eagle-import:SOT89")
      (libsource (lib "eagle-import") (part "LD2981ABU"))
    )
    (comp (ref "IC9")
      (value "LM4040B10")
      (footprint "eagle-import:DBZ_R-PDSO-G3")
      (libsource (lib "eagle-import") (part "LM4041DBZB12"))
    )
    (comp (ref "IC10")
      (value "7812T")
      (footprint "eagle-import:TO220H")
      (libsource (lib "eagle-import") (part "78T12"))
    )
    (comp (ref "IC11")
      (value "7912T")
      (footprint "eagle-import:TO220H")
      (libsource (lib "eagle-import") (part "79T12"))
    )
    (comp (ref "J1")
      (value "MTA04-156")
      (footprint "eagle-import:1X4MTA")
      (libsource (lib "eagle-import") (part "MTA04-156"))
    )
    (comp (ref "J11")
      (value "DOTCOMPOWER")
      (footprint "eagle-import:DOTCOMPOWER")
      (libsource (lib "eagle-import") (part "DOTCOMPOWER"))
    )
    (comp (ref "L1")
      (value "33u")
      (footprint "eagle-import:L2012C")
      (libsource (lib "eagle-import") (part "L-USL2012C"))
    )
    (comp (ref "L2")
      (value "WE-CBF_0805")
      (footprint "eagle-import:0805")
      (libsource (lib "eagle-import") (part "WE-CBF_0805"))
    )
    (comp (ref "L3")
      (value "WE-CBF_0805")
      (footprint "eagle-import:0805")
      (libsource (lib "eagle-import") (part "WE-CBF_0805"))
    )
    (comp (ref "L5")
      (value "WE-CBF_0805")
      (footprint "eagle-import:0805")
      (libsource (lib "eagle-import") (part "WE-CBF_0805"))
    )
    (comp (ref "R37")
      (value "2.2k")
      (footprint "eagle-import:R0805")
      (libsource (lib "eagle-import") (part "R-US_R0805"))
    )
  )
  (nets
    (net (code "1") (name "+3V3") (class "Default")
      (node (ref "C10") (pin "1") (pinfunction "1_1") (pintype "passive"))
      (node (ref "C16") (pin "+") (pinfunction "+_+") (pintype "passive"))
      (node (ref "C17") (pin "1") (pinfunction "1_1") (pintype "passive"))
      (node (ref "C25") (pin "1") (pinfunction "1_1") (pintype "passive"))
      (node (ref "C26") (pin "1") (pinfunction "1_1") (pintype "passive"))
      (node (ref "C3") (pin "+") (pinfunction "+_+") (pintype "passive"))
      (node (ref "C6") (pin "1") (pinfunction "1_1") (pintype "passive"))
      (node (ref "C9") (pin "1") (pinfunction "1_1") (pintype "passive"))
      (node (ref "D3") (pin "2") (pinfunction "C_2") (pintype "passive"))
      (node (ref "IC1") (pin "3") (pinfunction "VO_3") (pintype "passive"))
      (node (ref "IC4") (pin "1") (pinfunction "VBAT_1") (pintype "power_in"))
      (node (ref "IC4") (pin "17") (pinfunction "VDD_2_17") (pintype "power_in"))
      (node (ref "IC4") (pin "48") (pinfunction "VDD_1_48") (pintype "power_in"))
      (node (ref "IC5") (pin "11") (pinfunction "FLT_11") (pintype "input"))
      (node (ref "IC5") (pin "17") (pinfunction "XSMT_17") (pintype "input"))
      (node (ref "IC5") (pin "20") (pinfunction "DVDD_20") (pintype "power_in"))
      (node (ref "L4") (pin "2") (pinfunction "2_2") (pintype "passive"))
      (node (ref "LD1") (pin "A") (pinfunction "A_A") (pintype "passive"))
      (node (ref "LD2") (pin "A") (pinfunction "A_A") (pintype "passive"))
      (node (ref "LD3") (pin "A") (pinfunction "A_A") (pintype "passive"))
      (node (ref "LD4") (pin "A") (pinfunction "A_A") (pintype "passive"))
      (node (ref "LD5") (pin "A") (pinfunction "A_A") (pintype "passive"))
      (node (ref "LD6") (pin "A") (pinfunction "A_A") (pintype "passive"))
      (node (ref "LD7") (pin "A") (pinfunction "A_A") (pintype "passive"))
      (node (ref "LD8") (pin "A") (pinfunction "A_A") (pintype "passive"))
      (node (ref "R4") (pin "1") (pinfunction "1_1") (pintype "passive"))
    )
    (net (code "2") (name "+3V3_A") (class "Default")
      (node (ref "C19") (pin "1") (pinfunction "1_1") (pintype "passive"))
      (node (ref "C20") (pin "1") (pinfunction "1_1") (pintype "passive"))
      (node (ref "C22") (pin "+") (pinfunction "+_+") (pintype "passive"))
      (node (ref "C23") (pin "1") (pinfunction "1_1") (pintype "passive"))
      (node (ref "C24") (pin "1") (pinfunction "1_1") (pintype "passive"))
      (node (ref "C27") (pin "1") (pinfunction "1_1") (pintype "passive"))
      (node (ref "C28") (pin "1") (pinfunction "1_1") (pintype "passive"))
      (node (ref "C30") (pin "+") (pinfunction "+_+") (pintype "passive"))
      (node (ref "C36") (pin "1") (pinfunction "1_1") (pintype "passive"))
      (node (ref "C44") (pin "1") (pinfunction "1_1") (pintype "passive"))
      (node (ref "IC3") (pin "1") (pinfunction "VO_1") (pintype "passive"))
      (node (ref "IC4") (pin "24") (pinfunction "VDDSD_24") (pintype "power_in"))
      (node (ref "IC4") (pin "25") (pinfunction "VREFSD+_25") (pintype "power_in"))
      (node (ref "IC4") (pin "9") (pinfunction "VDDA_9") (pintype "power_in"))
      (node (ref "IC5") (pin "1") (pinfunction "CPVDD_1") (pintype "bidirectional"))
      (node (ref "IC5") (pin "8") (pinfunction "AVDD_8") (pintype "power_in"))
      (node (ref "IC6") (pin "4") (pinfunction "V+_4") (pintype "power_in"))
      (node (ref "IC7") (pin "4") (pinfunction "V+_4") (pintype "power_in"))
      (node (ref "R1") (pin "P$1") (pinfunction "E_P$1") (pintype "passive"))
      (node (ref "R2") (pin "P$1") (pinfunction "E_P$1") (pintype "passive"))
      (node (ref "R42") (pin "P$1") (pinfunction "E_P$1") (pintype "passive"))
      (node (ref "R43") (pin "P$1") (pinfunction "E_P$1") (pintype "passive"))
      (node (ref "R44") (pin "P$1") (pinfunction "E_P$1") (pintype "passive"))
      (node (ref "R7") (pin "P$1") (pinfunction "E_P$1") (pintype "passive"))
      (node (ref "R8") (pin "P$1") (pinfunction "E_P$1") (pintype "passive"))
    )
    (net (code "3") (name "ADC_FM") (class "Default")
      (node (ref "C40") (pin "2") (pinfunction "2_2") (pintype "passive"))
      (node (ref "IC4") (pin "22") (pinfunction "PE9/SDADC1_AIN7P/SDADC1_AIN8M/SDADC2_AIN7P/SDADC2_AIN8M_22") (pintype "bidirectional"))
      (node (ref "IC7") (pin "1") (pinfunction "OUT_1") (pintype "output"))
      (node (ref "R19") (pin "1") (pinfunction "1_1") (pintype "passive"))
    )
    (net (code "4") (name "ADC_GATE") (class "Default")
      (node (ref "C39") (pin "2") (pinfunction "2_2") (pintype "passive"))
      (node (ref "IC4") (pin "21") (pinfunction "PE8/SDADC1_AIN8P/SDADC2_AIN8P_21") (pintype "bidirectional"))
      (node (ref "IC6") (pin "14") (pinfunction "OUT_14") (pintype "output"))
      (node (ref "R18") (pin "1") (pinfunction "1_1") (pintype "passive"))
    )
    (net (code "5") (name "ADC_HARMONICS") (class "Default")
      (node (ref "C41") (pin "2") (pinfunction "2_2") (pintype "passive"))
      (node (ref "IC4") (pin "28") (pinfunction "PD8/SPI2_SCK/I2S2_CK/USART3_TX/SDADC3_AIN6P_28") (pintype "bidirectional"))
      (node (ref "IC7") (pin "14") (pinfunction "OUT_14") (pintype "output"))
      (node (ref "R20") (pin "1") (pinfunction "1_1") (pintype "passive"))
    )
    (net (code "6") (name "ADC_MODEL") (class "Default")
      (node (ref "C46") (pin "2") (pinfunction "2_2") (pintype "passive"))
      (node (ref "IC4") (pin "19") (pinfunction "PB1/TIM3_CH4/ADC_IN9/SDADC1_AIN5P/SDADC1_AIN6M_19") (pintype "bidirectional"))
      (node (ref "IC6") (pin "7") (pinfunction "OUT_7") (pintype "output"))
      (node (ref "R31") (pin "1") (pinfunction "1_1") (pintype "passive"))
    )
    (net (code "7") (name "ADC_MORPH") (class "Default")
      (node (ref "C49") (pin "2") (pinfunction "2_2") (pintype "passive"))
      (node (ref "IC4") (pin "27") (pinfunction "PB15/SPI2_MOSI/I2S2_SD/SDADC3_AIN7P/SDADC3_AIN8M_27") (pintype "bidirectional"))
      (node (ref "IC7") (pin "8") (pinfunction "OUT_8") (pintype "output"))
      (node (ref "R35") (pin "1") (pinfunction "1_1") (pintype "passive"))
    )
    (net (code "8") (name "ADC_TIMBRE") (class "Default")
      (node (ref "C47") (pin "2") (pinfunction "2_2") (pintype "passive"))
      (node (ref "IC4") (pin "20") (pinfunction "PB2/SDADC1_AIN4P/SDADC2_AIN6P_20") (pintype "bidirectional"))
      (node (ref "IC6") (pin "8") (pinfunction "OUT_8") (pintype "output"))
      (node (ref "R32") (pin "1") (pinfunction "1_1") (pintype "passive"))
    )
    (net (code "9") (name "ADC_TRIG") (class "Default")
      (node (ref "C38") (pin "2") (pinfunction "2_2") (pintype "passive"))
      (node (ref "IC4") (pin "18") (pinfunction "PB0/SPI1_MOSI/I2S1_SD/TIM3_CH3/ADC_IN8/SDADC1_AIN6P_18") (pintype "bidirectional"))
      (node (ref "IC6") (pin "1") (pinfunction "OUT_1") (pintype "output"))
      (node (ref "R17") (pin "1") (pinfunction "1_1") (pintype "passive"))
    )
    (net (code "10") (name "ADC_V_OCT") (class "Default")
      (node (ref "C48") (pin "2") (pinfunction "2_2") (pintype "passive"))
      (node (ref "IC4") (pin "26") (pinfunction "PB14/SPI2_MISO/I2S2_MCK/USART3_RTS/SDADC3_AIN8P_26") (pintype "bidirectional"))
      (node (ref "IC7") (pin "7") (pinfunction "OUT_7") (pintype "output"))
      (node (ref "R34") (pin "1") (pinfunction "1_1") (pintype "passive"))
    )
    (net (code "11") (name "AREF_-10") (class "Default")
      (node (ref "C50") (pin "1") (pinfunction "1_1") (pintype "passive"))
      (node (ref "IC9") (pin "2") (pinfunction "A_2") (pintype "passive"))
      (node (ref "R23") (pin "2") (pinfunction "2_2") (pintype "passive"))
      (node (ref "R25") (pin "2") (pinfunction "2_2") (pintype "passive"))
      (node (ref "R26") (pin "2") (pinfunction "2_2") (pintype "passive"))
      (node (ref "R27") (pin "2") (pinfunction "2_2") (pintype "passive"))
      (node (ref "R29") (pin "2") (pinfunction "2_2") (pintype "passive"))
      (node (ref "R30") (pin "2") (pinfunction "2_2") (pintype "passive"))
      (node (ref "R33") (pin "2") (pinfunction "2_2") (pintype "passive"))
      (node (ref "R36") (pin "2") (pinfunction "2_2") (pintype "passive"))
      (node (ref "R37") (pin "2") (pinfunction "2_2") (pintype "passive"))
    )
    (net (code "12") (name "DAC_BCK") (class "Default")
      (node (ref "IC4") (pin "29") (pinfunction "PA8/SPI2_SCK/I2S2_CK/I2C2_SMBA/USART1_CK/TIM5_CH1_29") (pintype "bidirectional"))
      (node (ref "IC5") (pin "13") (pinfunction "BCK_13") (pintype "input"))
    )
    (net (code "13") (name "DAC_DIN") (class "Default")
      (node (ref "IC4") (pin "31") (pinfunction "PA10/SPI2_MOSI/I2S2_SD/I2C2_SDA/USART1_RX/TIM2_CH4_31") (pintype "bidirectional"))
      (node (ref "IC5") (pin "14") (pinfunction "DIN_14") (pintype "input"))
    )
    (net (code "14") (name "DAC_LRCK") (class "Default")
      (node (ref "IC4") (pin "32") (pinfunction "PA11/SPI2_NSS/I2S2_WS/SPI1_NSS/I2S1_WS/USART1_CTS/CAN_RX/TIM4_CH1/TIM5_CH2_32") (pintype "bidirectional"))
      (node (ref "IC5") (pin "15") (pinfunction "LRCK_15") (pintype "input"))
    )
    (net (code "15") (name "FREQ_ATT") (class "Default")
      (node (ref "C51") (pin "1") (pinfunction "1_1") (pintype "passive"))
      (node (ref "IC4") (pin "15") (pinfunction "PA5/SPI1_SCK/I2S1_CK/TIM2_CH1/ADC_IN5/DAC1_OUT2_15") (pintype "bidirectional"))
      (node (ref "R43") (pin "P$2") (pinfunction "S_P$2") (pintype "passive"))
    )
    (net (code "16") (name "FREQ_POT") (class "Default")
      (node (ref "C11") (pin "1") (pinfunction "1_1") (pintype "passive"))
      (node (ref "IC4") (pin "10") (pinfunction "PA0/USART2_CTS/TIM2_CH1/TIM5_CH1/ADC_IN0_10") (pintype "bidirectional"))
      (node (ref "R1") (pin "P$2") (pinfunction "S_P$2") (pintype "passive"))
    )
    (net (code "17") (name "GND") (class "Default")
      (node (ref "C1") (pin "2") (pinfunction "2_2") (pintype "passive"))
      (node (ref "C10") (pin "2") (pinfunction "2_2") (pintype "passive"))
      (node (ref "C11") (pin "2") (pinfunction "2_2") (pintype "passive"))
      (node (ref "C12") (pin "2") (pinfunction "2_2") (pintype "passive"))
      (node (ref "C13") (pin "2") (pinfunction "2_2") (pintype "passive"))
      (node (ref "C14") (pin "1") (pinfunction "1_1") (pintype "passive"))
      (node (ref "C15") (pin "2") (pinfunction "2_2") (pintype "passive"))
      (node (ref "C16") (pin "-") (pinfunction "-_-") (pintype "passive"))
      (node (ref "C17") (pin "2") (pinfunction "2_2") (pintype "passive"))
      (node (ref "C18") (pin "2") (pinfunction "2_2") (pintype "passive"))
      (node (ref "C19") (pin "2") (pinfunction "2_2") (pintype "passive"))
      (node (ref "C2") (pin "2") (pinfunction "2_2") (pintype "passive"))
      (node (ref "C20") (pin "2") (pinfunction "2_2") (pintype "passive"))
      (node (ref "C21") (pin "1") (pinfunction "1_1") (pintype "passive"))
      (node (ref "C22") (pin "-") (pinfunction "-_-") (pintype "passive"))
      (node (ref "C23") (pin "2") (pinfunction "2_2") (pintype "passive"))
      (node (ref "C24") (pin "2") (pinfunction "2_2") (pintype "passive"))
      (node (ref "C25") (pin "2") (pinfunction "2_2") (pintype "passive"))
      (node (ref "C26") (pin "2") (pinfunction "2_2") (pintype "passive"))
      (node (ref "C27") (pin "2") (pinfunction "2_2") (pintype "passive"))
      (node (ref "C28") (pin "2") (pinfunction "2_2") (pintype "passive"))
      (node (ref "C3") (pin "-") (pinfunction "-_-") (pintype "passive"))
      (node (ref "C30") (pin "-") (pinfunction "-_-") (pintype "passive"))
      (node (ref "C31") (pin "2") (pinfunction "2_2") (pintype "passive"))
      (node (ref "C32") (pin "2") (pinfunction "2_2") (pintype "passive"))
      (node (ref "C33") (pin "2") (pinfunction "2_2") (pintype "passive"))
      (node (ref "C34") (pin "2") (pinfunction "2_2") (pintype "passive"))
      (node (ref "C35") (pin "2") (pinfunction "2_2") (pintype "passive"))
      (node (ref "C36") (pin "2") (pinfunction "2_2") (pintype "passive"))
      (node (ref "C37") (pin "2") (pinfunction "2_2") (pintype "passive"))
      (node (ref "C4") (pin "-") (pinfunction "-_-") (pintype "passive"))
      (node (ref "C44") (pin "2") (pinfunction "2_2") (pintype "passive"))
      (node (ref "C45") (pin "1") (pinfunction "1_1") (pintype "passive"))
      (node (ref "C5") (pin "+") (pinfunction "+_+") (pintype "passive"))
      (node (ref "C50") (pin "2") (pinfunction "2_2") (pintype "passive"))
      (node (ref "C51") (pin "2") (pinfunction "2_2") (pintype "passive"))
      (node (ref "C52") (pin "2") (pinfunction "2_2") (pintype "passive"))
      (node (ref "C53") (pin "2") (pinfunction "2_2") (pintype "passive"))
      (node (ref "C6") (pin "2") (pinfunction "2_2") (pintype "passive"))
      (node (ref "C62") (pin "2") (pinfunction "2_2") (pintype "passive"))
      (node (ref "C63") (pin "2") (pinfunction "2_2") (pintype "passive"))
      (node (ref "C64") (pin "1") (pinfunction "1_1") (pintype "passive"))
      (node (ref "C65") (pin "1") (pinfunction "1_1") (pintype "passive"))
      (node (ref "C7") (pin "-") (pinfunction "-_-") (pintype "passive"))
      (node (ref "C8") (pin "2") (pinfunction "2_2") (pintype "passive"))
      (node (ref "C9") (pin "2") (pinfunction "2_2") (pintype "passive"))
      (node (ref "D3") (pin "1") (pinfunction "A_1") (pintype "passive"))
      (node (ref "IC1") (pin "2") (pinfunction "GND_2") (pintype "passive"))
      (node (ref "IC10") (pin "2") (pinfunction "GND_2") (pintype "passive"))
      (node (ref "IC11") (pin "1") (pinfunction "GND_1") (pintype "passive"))
      (node (ref "IC2") (pin "1") (pinfunction "GND_1") (pintype "bidirectional"))
      (node (ref "IC2") (pin "21") (pinfunction "BLANK_21") (pintype "bidirectional"))
      (node (ref "IC3") (pin "2") (pinfunction "GND_2") (pintype "passive"))
      (node (ref "IC4") (pin "23") (pinfunction "VSSSD/VREFSD-_23") (pintype "power_in"))
      (node (ref "IC4") (pin "44") (pinfunction "BOOT0_44") (pintype "bidirectional"))
      (node (ref "IC4") (pin "47") (pinfunction "VSS_1_47") (pintype "power_in"))
      (node (ref "IC4") (pin "8") (pinfunction "VSSA_8") (pintype "power_in"))
      (node (ref "IC5") (pin "10") (pinfunction "DEMP_10") (pintype "input"))
      (node (ref "IC5") (pin "12") (pinfunction "SCK_12") (pintype "input"))
      (node (ref "IC5") (pin "16") (pinfunction "FMT_16") (pintype "input"))
      (node (ref "IC5") (pin "19") (pinfunction "DGND_19") (pintype "power_in"))
      (node (ref "IC5") (pin "3") (pinfunction "CPGND_3") (pintype "bidirectional"))
      (node (ref "IC5") (pin "9") (pinfunction "AGND_9") (pintype "power_in"))
      (node (ref "IC6") (pin "10") (pinfunction "+IN_10") (pintype "input"))
      (node (ref "IC6") (pin "11") (pinfunction "V-_11") (pintype "power_in"))
      (node (ref "IC6") (pin "12") (pinfunction "+IN_12") (pintype "input"))
      (node (ref "IC6") (pin "3") (pinfunction "+IN_3") (pintype "input"))
      (node (ref "IC6") (pin "5") (pinfunction "+IN_5") (pintype "input"))
      (node (ref "IC7") (pin "10") (pinfunction "+IN_10") (pintype "input"))
      (node (ref "IC7") (pin "11") (pinfunction "V-_11") (pintype "power_in"))
      (node (ref "IC7") (pin "12") (pinfunction "+IN_12") (pintype "input"))
      (node (ref "IC7") (pin "3") (pinfunction "+IN_3") (pintype "input"))
      (node (ref "IC7") (pin "5") (pinfunction "+IN_5") (pintype "input"))
      (node (ref "IC8") (pin "3") (pinfunction "+IN_3") (pintype "input"))
      (node (ref "IC8") (pin "5") (pinfunction "+IN_5") (pintype "input"))
      (node (ref "IC9") (pin "1") (pinfunction "C_1") (pintype "passive"))
      (node (ref "J1") (pin "2") (pinfunction "2_2") (pintype "passive"))
      (node (ref "J1") (pin "3") (pinfunction "3_3") (pintype "passive"))
      (node (ref "J11") (pin "4") (pinfunction "4_4") (pintype "passive"))
      (node (ref "JP6") (pin "1") (pinfunction "1_1") (pintype "passive"))
      (node (ref "Q1") (pin "2") (pinfunction "LID1_2") (pintype "power_in"))
      (node (ref "Q1") (pin "4") (pinfunction "LID2_4") (pintype "power_in"))
      (node (ref "R1") (pin "P$3") (pinfunction "A_P$3") (pintype "passive"))
      (node (ref "R2") (pin "P$3") (pinfunction "A_P$3") (pintype "passive"))
      (node (ref "R3") (pin "2") (pinfunction "2_2") (pintype "passive"))
      (node (ref "R42") (pin "P$3") (pinfunction "A_P$3") (pintype "passive"))
      (node (ref "R43") (pin "P$3") (pinfunction "A_P$3") (pintype "passive"))
      (node (ref "R44") (pin "P$3") (pinfunction "A_P$3") (pintype "passive"))
      (node (ref "R7") (pin "P$3") (pinfunction "A_P$3") (pintype "passive"))
      (node (ref "R8") (pin "P$3") (pinfunction "A_P$3") (pintype "passive"))
      (node (ref "SV1") (pin "3") (pinfunction "3_3") (pintype "passive"))
      (node (ref "SV1") (pin "4") (pinfunction "4_4") (pintype "passive"))
      (node (ref "SV2") (pin "10") (pinfunction "10_10") (pintype "passive"))
      (node (ref "SW1") (pin "1") (pinfunction "1_1") (pintype "passive"))
      (node (ref "SW1") (pin "2") (pinfunction "2_2") (pintype "passive"))
      (node (ref "SW2") (pin "1") (pinfunction "1_1") (pintype "passive"))
      (node (ref "SW2") (pin "2") (pinfunction "2_2") (pintype "passive"))
    )
    (net (code "18") (name "HARMONICS_POT") (class "Default")
      (node (ref "C12") (pin "1") (pinfunction "1_1") (pintype "passive"))
      (node (ref "IC4") (pin "12") (pinfunction "PA2/SPI3_MISO/I2S3_MCK/USART2_TX/TIM2_CH3/TIM5_CH3/ADC_IN2_12") (pintype "bidirectional"))
      (node (ref "R2") (pin "P$2") (pinfunction "S_P$2") (pintype "passive"))
    )
    (net (code "19") (name "LEDS_SCK") (class "Default")
      (node (ref "IC2") (pin "3") (pinfunction "SCLK_3") (pintype "bidirectional"))
      (node (ref "IC4") (pin "33") (pinfunction "PA12/SPI1_SCK/I2S1_CK/USART1_RTS/CAN_TX/TIM4_CH2/TIM5_CH3_33") (pintype "bidirectional"))
    )
    (net (code "20") (name "LEDS_SIN") (class "Default")
      (node (ref "IC2") (pin "2") (pinfunction "SIN_2") (pintype "bidirectional"))
      (node (ref "IC4") (pin "35") (pinfunction "PF6/SPI1_MOSI/I2S1_SD/USART3_RTS/TIM4_CH4/I2C2_SCL_35") (pintype "bidirectional"))
    )
    (net (code "21") (name "LEDS_SS") (class "Default")
      (node (ref "IC2") (pin "4") (pinfunction "LAT_4") (pintype "bidirectional"))
      (node (ref "IC4") (pin "36") (pinfunction "PF7/I2C2_SDA/USART2_CK_36") (pintype "bidirectional"))
    )
    (net (code "22") (name "MORPH_ATT") (class "Default")
      (node (ref "C52") (pin "1") (pinfunction "1_1") (pintype "passive"))
      (node (ref "IC4") (pin "14") (pinfunction "PA4/SPI1_NSS/I2S1_WS/SPI3_NSS/I2S3_WS/USART2_CK/TIM3_CH2/ADC_IN4/DAC1_OUT1_14") (pintype "bidirectional"))
      (node (ref "R44") (pin "P$2") (pinfunction "S_P$2") (pintype "passive"))
    )
    (net (code "23") (name "MORPH_POT") (class "Default")
      (node (ref "C34") (pin "1") (pinfunction "1_1") (pintype "passive"))
      (node (ref "IC4") (pin "11") (pinfunction "PA1/SPI3_SCK/I2S3_CK/USART2_RTS/TIM2_CH2/TIM5_CH2/ADC_IN1_11") (pintype "bidirectional"))
      (node (ref "R8") (pin "P$2") (pinfunction "S_P$2") (pintype "passive"))
    )
    (net (code "24") (name "NORMALIZATION_PROBE") (class "Default")
      (node (ref "D3") (pin "3") (pinfunction "AC_3") (pintype "passive"))
      (node (ref "IC4") (pin "30") (pinfunction "PA9/SPI_MISO/I2S2_MCK/I2C2_SCL/USART1_TX/TIM2_CH3_30") (pintype "bidirectional"))
      (node (ref "SV2") (pin "5") (pinfunction "5_5") (pintype "passive"))
    )
    (net (code "25") (name "Net-(C21-Pad2)") (class "Default")
      (node (ref "C21") (pin "2") (pinfunction "2_2") (pintype "passive"))
      (node (ref "Q1") (pin "1") (pinfunction "1_1") (pintype "passive"))
      (node (ref "R6") (pin "2") (pinfunction "2_2") (pintype "passive"))
    )
    (net (code "26") (name "Net-(C33-Pad1)") (class "Default")
      (node (ref "C33") (pin "1") (pinfunction "1_1") (pintype "passive"))
      (node (ref "R11") (pin "1") (pinfunction "1_1") (pintype "passive"))
      (node (ref "R21") (pin "2") (pinfunction "2_2") (pintype "passive"))
    )
    (net (code "27") (name "Net-(C35-Pad1)") (class "Default")
      (node (ref "C35") (pin "1") (pinfunction "1_1") (pintype "passive"))
      (node (ref "R12") (pin "1") (pinfunction "1_1") (pintype "passive"))
      (node (ref "R16") (pin "2") (pinfunction "2_2") (pintype "passive"))
    )
    (net (code "28") (name "Net-(D1-PadA)") (class "Default")
      (node (ref "D1") (pin "A") (pinfunction "A_A") (pintype "passive"))
      (node (ref "J1") (pin "1") (pinfunction "1_1") (pintype "passive"))
      (node (ref "J11") (pin "1") (pinfunction "1_1") (pintype "passive"))
    )
    (net (code "29") (name "Net-(D2-PadC)") (class "Default")
      (node (ref "D2") (pin "C") (pinfunction "C_C") (pintype "passive"))
      (node (ref "J1") (pin "4") (pinfunction "4_4") (pintype "passive"))
      (node (ref "J11") (pin "5") (pinfunction "5_5") (pintype "passive"))
    )
    (net (code "30") (name "Net-(IC1-VI)") (class "Default")
      (node (ref "C1") (pin "1") (pinfunction "1_1") (pintype "passive"))
      (node (ref "IC1") (pin "1") (pinfunction "VI_1") (pintype "input"))
      (node (ref "L1") (pin "2") (pinfunction "2_2") (pintype "passive"))
    )
    (net (code "31") (name "Net-(IC2-IREF)") (class "Default")
      (node (ref "IC2") (pin "23") (pinfunction "IREF_23") (pintype "bidirectional"))
      (node (ref "R3") (pin "1") (pinfunction "1_1") (pintype "passive"))
    )
    (net (code "32") (name "Net-(IC2-OUT0)") (class "Default")
      (node (ref "IC2") (pin "5") (pinfunction "OUT0_5") (pintype "bidirectional"))
      (node (ref "LD5") (pin "CR") (pinfunction "CR_CR") (pintype "passive"))
    )
    (net (code "33") (name "Net-(IC2-OUT1)") (class "Default")
      (node (ref "IC2") (pin "6") (pinfunction "OUT1_6") (pintype "bidirectional"))
      (node (ref "LD5") (pin "CX") (pinfunction "CG_CX") (pintype "passive"))
    )
    (net (code "34") (name "Net-(IC2-OUT2)") (class "Default")
      (node (ref "IC2") (pin "7") (pinfunction "OUT2_7") (pintype "bidirectional"))
      (node (ref "LD6") (pin "CR") (pinfunction "CR_CR") (pintype "passive"))
    )
    (net (code "35") (name "Net-(IC2-OUT3)") (class "Default")
      (node (ref "IC2") (pin "8") (pinfunction "OUT3_8") (pintype "bidirectional"))
      (node (ref "LD6") (pin "CX") (pinfunction "CG_CX") (pintype "passive"))
    )
    (net (code "36") (name "Net-(IC2-OUT4)") (class "Default")
      (node (ref "IC2") (pin "9") (pinfunction "OUT4_9") (pintype "bidirectional"))
      (node (ref "LD7") (pin "CR") (pinfunction "CR_CR") (pintype "passive"))
    )
    (net (code "37") (name "Net-(IC2-OUT5)") (class "Default")
      (node (ref "IC2") (pin "10") (pinfunction "OUT5_10") (pintype "bidirectional"))
      (node (ref "LD7") (pin "CX") (pinfunction "CG_CX") (pintype "passive"))
    )
    (net (code "38") (name "Net-(IC2-OUT6)") (class "Default")
      (node (ref "IC2") (pin "11") (pinfunction "OUT6_11") (pintype "bidirectional"))
      (node (ref "LD8") (pin "CR") (pinfunction "CR_CR") (pintype "passive"))
    )
    (net (code "39") (name "Net-(IC2-OUT7)") (class "Default")
      (node (ref "IC2") (pin "12") (pinfunction "OUT7_12") (pintype "bidirectional"))
      (node (ref "LD8") (pin "CX") (pinfunction "CG_CX") (pintype "passive"))
    )
    (net (code "40") (name "Net-(IC2-OUT8)") (class "Default")
      (node (ref "IC2") (pin "13") (pinfunction "OUT8_13") (pintype "bidirectional"))
      (node (ref "LD4") (pin "CR") (pinfunction "CR_CR") (pintype "passive"))
    )
    (net (code "41") (name "Net-(IC2-OUT9)") (class "Default")
      (node (ref "IC2") (pin "14") (pinfunction "OUT9_14") (pintype "bidirectional"))
      (node (ref "LD4") (pin "CX") (pinfunction "CG_CX") (pintype "passive"))
    )
    (net (code "42") (name "Net-(IC2-OUT10)") (class "Default")
      (node (ref "IC2") (pin "15") (pinfunction "OUT10_15") (pintype "bidirectional"))
      (node (ref "LD3") (pin "CR") (pinfunction "CR_CR") (pintype "passive"))
    )
    (net (code "43") (name "Net-(IC2-OUT11)") (class "Default")
      (node (ref "IC2") (pin "16") (pinfunction "OUT11_16") (pintype "bidirectional"))
      (node (ref "LD3") (pin "CX") (pinfunction "CG_CX") (pintype "passive"))
    )
    (net (code "44") (name "Net-(IC2-OUT12)") (class "Default")
      (node (ref "IC2") (pin "17") (pinfunction "OUT12_17") (pintype "bidirectional"))
      (node (ref "LD2") (pin "CR") (pinfunction "CR_CR") (pintype "passive"))
    )
    (net (code "45") (name "Net-(IC2-OUT13)") (class "Default")
      (node (ref "IC2") (pin "18") (pinfunction "OUT13_18") (pintype "bidirectional"))
      (node (ref "LD2") (pin "CX") (pinfunction "CG_CX") (pintype "passive"))
    )
    (net (code "46") (name "Net-(IC2-OUT14)") (class "Default")
      (node (ref "IC2") (pin "19") (pinfunction "OUT14_19") (pintype "bidirectional"))
      (node (ref "LD1") (pin "CR") (pinfunction "CR_CR") (pintype "passive"))
    )
    (net (code "47") (name "Net-(IC2-OUT15)") (class "Default")
      (node (ref "IC2") (pin "20") (pinfunction "OUT15_20") (pintype "bidirectional"))
      (node (ref "LD1") (pin "CX") (pinfunction "CG_CX") (pintype "passive"))
    )
    (net (code "48") (name "Net-(IC2-VCC)") (class "Default")
      (node (ref "C7") (pin "+") (pinfunction "+_+") (pintype "passive"))
      (node (ref "C8") (pin "1") (pinfunction "1_1") (pintype "passive"))
      (node (ref "IC2") (pin "24") (pinfunction "VCC_24") (pintype "bidirectional"))
      (node (ref "L4") (pin "1") (pinfunction "1_1") (pintype "passive"))
    )
    (net (code "49") (name "Net-(IC3-VI)") (class "Default")
      (node (ref "C13") (pin "1") (pinfunction "1_1") (pintype "passive"))
      (node (ref "IC3") (pin "3") (pinfunction "VI_3") (pintype "input"))
      (node (ref "L5") (pin "1") (pinfunction "1_1") (pintype "passive"))
    )
    (net (code "50") (name "Net-(IC4-PF0{slash}OSC_IN{slash}I2C2_SDA)") (class "Default")
      (node (ref "IC4") (pin "5") (pinfunction "PF0/OSC_IN/I2C2_SDA_5") (pintype "bidirectional"))
      (node (ref "R5") (pin "1") (pinfunction "1_1") (pintype "passive"))
    )
    (net (code "51") (name "Net-(IC4-PF1{slash}OSC_OUT{slash}I2C2_SCL)") (class "Default")
      (node (ref "IC4") (pin "6") (pinfunction "PF1/OSC_OUT/I2C2_SCL_6") (pintype "bidirectional"))
      (node (ref "R6") (pin "1") (pinfunction "1_1") (pintype "passive"))
    )
    (net (code "52") (name "Net-(IC5-CAPM)") (class "Default")
      (node (ref "C29") (pin "2") (pinfunction "2_2") (pintype "passive"))
      (node (ref "IC5") (pin "4") (pinfunction "CAPM_4") (pintype "bidirectional"))
    )
    (net (code "53") (name "Net-(IC5-CAPP)") (class "Default")
      (node (ref "C29") (pin "1") (pinfunction "1_1") (pintype "passive"))
      (node (ref "IC5") (pin "2") (pinfunction "CAPP_2") (pintype "bidirectional"))
    )
    (net (code "54") (name "Net-(IC5-LDOO)") (class "Default")
      (node (ref "C18") (pin "1") (pinfunction "1_1") (pintype "passive"))
      (node (ref "IC5") (pin "18") (pinfunction "LDOO_18") (pintype "bidirectional"))
    )
    (net (code "55") (name "Net-(IC5-OUTL)") (class "Default")
      (node (ref "IC5") (pin "6") (pinfunction "OUTL_6") (pintype "output"))
      (node (ref "R11") (pin "2") (pinfunction "2_2") (pintype "passive"))
    )
    (net (code "56") (name "Net-(IC5-OUTR)") (class "Default")
      (node (ref "IC5") (pin "7") (pinfunction "OUTR_7") (pintype "output"))
      (node (ref "R12") (pin "2") (pinfunction "2_2") (pintype "passive"))
    )
    (net (code "57") (name "Net-(IC5-VNEG)") (class "Default")
      (node (ref "C31") (pin "1") (pinfunction "1_1") (pintype "passive"))
      (node (ref "IC5") (pin "5") (pinfunction "VNEG_5") (pintype "input"))
    )
    (net (code "58") (name "Net-(IC6A--IN)") (class "Default")
      (node (ref "C38") (pin "1") (pinfunction "1_1") (pintype "passive"))
      (node (ref "IC6") (pin "2") (pinfunction "-IN_2") (pintype "input"))
      (node (ref "R17") (pin "2") (pinfunction "2_2") (pintype "passive"))
      (node (ref "R24") (pin "1") (pinfunction "1_1") (pintype "passive"))
      (node (ref "R25") (pin "1") (pinfunction "1_1") (pintype "passive"))
    )
    (net (code "59") (name "Net-(IC6B--IN)") (class "Default")
      (node (ref "C46") (pin "1") (pinfunction "1_1") (pintype "passive"))
      (node (ref "IC6") (pin "6") (pinfunction "-IN_6") (pintype "input"))
      (node (ref "R30") (pin "1") (pinfunction "1_1") (pintype "passive"))
      (node (ref "R31") (pin "2") (pinfunction "2_2") (pintype "passive"))
      (node (ref "R40") (pin "1") (pinfunction "1_1") (pintype "passive"))
    )
    (net (code "60") (name "Net-(IC6C--IN)") (class "Default")
      (node (ref "C47") (pin "1") (pinfunction "1_1") (pintype "passive"))
      (node (ref "IC6") (pin "9") (pinfunction "-IN_9") (pintype "input"))
      (node (ref "R32") (pin "2") (pinfunction "2_2") (pintype "passive"))
      (node (ref "R33") (pin "1") (pinfunction "1_1") (pintype "passive"))
      (node (ref "R41") (pin "1") (pinfunction "1_1") (pintype "passive"))
    )
    (net (code "61") (name "Net-(IC6D--IN)") (class "Default")
      (node (ref "C39") (pin "1") (pinfunction "1_1") (pintype "passive"))
      (node (ref "IC6") (pin "13") (pinfunction "-IN_13") (pintype "input"))
      (node (ref "R14") (pin "1") (pinfunction "1_1") (pintype "passive"))
      (node (ref "R18") (pin "2") (pinfunction "2_2") (pintype "passive"))
      (node (ref "R26") (pin "1") (pinfunction "1_1") (pintype "passive"))
    )
    (net (code "62") (name "Net-(IC7A--IN)") (class "Default")
      (node (ref "C40") (pin "1") (pinfunction "1_1") (pintype "passive"))
      (node (ref "IC7") (pin "2") (pinfunction "-IN_2") (pintype "input"))
      (node (ref "R15") (pin "1") (pinfunction "1_1") (pintype "passive"))
      (node (ref "R19") (pin "2") (pinfunction "2_2") (pintype "passive"))
      (node (ref "R23") (pin "1") (pinfunction "1_1") (pintype "passive"))
    )
    (net (code "63") (name "Net-(IC7B--IN)") (class "Default")
      (node (ref "C48") (pin "1") (pinfunction "1_1") (pintype "passive"))
      (node (ref "IC7") (pin "6") (pinfunction "-IN_6") (pintype "input"))
      (node (ref "R29") (pin "1") (pinfunction "1_1") (pintype "passive"))
      (node (ref "R34") (pin "2") (pinfunction "2_2") (pintype "passive"))
      (node (ref "R38") (pin "1") (pinfunction "1_1") (pintype "passive"))
    )
    (net (code "64") (name "Net-(IC7C--IN)") (class "Default")
      (node (ref "C49") (pin "1") (pinfunction "1_1") (pintype "passive"))
      (node (ref "IC7") (pin "9") (pinfunction "-IN_9") (pintype "input"))
      (node (ref "R35") (pin "2") (pinfunction "2_2") (pintype "passive"))
      (node (ref "R36") (pin "1") (pinfunction "1_1") (pintype "passive"))
      (node (ref "R39") (pin "1") (pinfunction "1_1") (pintype "passive"))
    )
    (net (code "65") (name "Net-(IC7D--IN)") (class "Default")
      (node (ref "C41") (pin "1") (pinfunction "1_1") (pintype "passive"))
      (node (ref "IC7") (pin "13") (pinfunction "-IN_13") (pintype "input"))
      (node (ref "R13") (pin "1") (pinfunction "1_1") (pintype "passive"))
      (node (ref "R20") (pin "2") (pinfunction "2_2") (pintype "passive"))
      (node (ref "R27") (pin "1") (pinfunction "1_1") (pintype "passive"))
    )
    (net (code "66") (name "Net-(IC8A--IN)") (class "Default")
      (node (ref "C42") (pin "1") (pinfunction "1_1") (pintype "passive"))
      (node (ref "IC8") (pin "2") (pinfunction "-IN_2") (pintype "input"))
      (node (ref "R21") (pin "1") (pinfunction "1_1") (pintype "passive"))
      (node (ref "R22") (pin "2") (pinfunction "2_2") (pintype "passive"))
    )
    (net (code "67") (name "Net-(IC8A-OUT)") (class "Default")
      (node (ref "C42") (pin "2") (pinfunction "2_2") (pintype "passive"))
      (node (ref "IC8") (pin "1") (pinfunction "OUT_1") (pintype "output"))
      (node (ref "R22") (pin "1") (pinfunction "1_1") (pintype "passive"))
      (node (ref "SV1") (pin "1") (pinfunction "1_1") (pintype "passive"))
    )
    (net (code "68") (name "Net-(IC8B--IN)") (class "Default")
      (node (ref "C43") (pin "1") (pinfunction "1_1") (pintype "passive"))
      (node (ref "IC8") (pin "6") (pinfunction "-IN_6") (pintype "input"))
      (node (ref "R16") (pin "1") (pinfunction "1_1") (pintype "passive"))
      (node (ref "R28") (pin "2") (pinfunction "2_2") (pintype "passive"))
    )
    (net (code "69") (name "Net-(IC8B-OUT)") (class "Default")
      (node (ref "C43") (pin "2") (pinfunction "2_2") (pintype "passive"))
      (node (ref "IC8") (pin "7") (pinfunction "OUT_7") (pintype "output"))
      (node (ref "R28") (pin "1") (pinfunction "1_1") (pintype "passive"))
      (node (ref "SV1") (pin "2") (pinfunction "2_2") (pintype "passive"))
    )
    (net (code "70") (name "Net-(IC10-VI)") (class "Default")
      (node (ref "C63") (pin "1") (pinfunction "1_1") (pintype "passive"))
      (node (ref "D1") (pin "C") (pinfunction "C_C") (pintype "passive"))
      (node (ref "IC10") (pin "1") (pinfunction "VI_1") (pintype "input"))
    )
    (net (code "71") (name "Net-(IC10-VO)") (class "Default")
      (node (ref "C2") (pin "1") (pinfunction "1_1") (pintype "passive"))
      (node (ref "C62") (pin "1") (pinfunction "1_1") (pintype "passive"))
      (node (ref "IC10") (pin "3") (pinfunction "VO_3") (pintype "passive"))
      (node (ref "L1") (pin "1") (pinfunction "1_1") (pintype "passive"))
      (node (ref "L2") (pin "2") (pinfunction "2_2") (pintype "passive"))
      (node (ref "L5") (pin "2") (pinfunction "2_2") (pintype "passive"))
    )
    (net (code "72") (name "Net-(IC11-VI)") (class "Default")
      (node (ref "C65") (pin "2") (pinfunction "2_2") (pintype "passive"))
      (node (ref "D2") (pin "A") (pinfunction "A_A") (pintype "passive"))
      (node (ref "IC11") (pin "2") (pinfunction "VI_2") (pintype "input"))
    )
    (net (code "73") (name "Net-(IC11-VO)") (class "Default")
      (node (ref "C64") (pin "2") (pinfunction "2_2") (pintype "passive"))
      (node (ref "IC11") (pin "3") (pinfunction "VO_3") (pintype "passive"))
      (node (ref "L3") (pin "2") (pinfunction "2_2") (pintype "passive"))
    )
    (net (code "74") (name "Net-(JP5-Pad1)") (class "Default")
      (node (ref "JP5") (pin "1") (pinfunction "1_1") (pintype "passive"))
      (node (ref "R9") (pin "1") (pinfunction "1_1") (pintype "passive"))
    )
    (net (code "75") (name "Net-(JP5-Pad2)") (class "Default")
      (node (ref "JP5") (pin "2") (pinfunction "2_2") (pintype "passive"))
      (node (ref "R10") (pin "1") (pinfunction "1_1") (pintype "passive"))
    )
    (net (code "76") (name "Net-(Q1B-2)") (class "Default")
      (node (ref "C14") (pin "2") (pinfunction "2_2") (pintype "passive"))
      (node (ref "Q1") (pin "3") (pinfunction "2_3") (pintype "passive"))
      (node (ref "R5") (pin "2") (pinfunction "2_2") (pintype "passive"))
    )
    (net (code "77") (name "Net-(R13-Pad2)") (class "Default")
      (node (ref "R13") (pin "2") (pinfunction "2_2") (pintype "passive"))
      (node (ref "SV2") (pin "8") (pinfunction "8_8") (pintype "passive"))
    )
    (net (code "78") (name "Net-(R14-Pad2)") (class "Default")
      (node (ref "R14") (pin "2") (pinfunction "2_2") (pintype "passive"))
      (node (ref "SV2") (pin "4") (pinfunction "4_4") (pintype "passive"))
    )
    (net (code "79") (name "Net-(R15-Pad2)") (class "Default")
      (node (ref "R15") (pin "2") (pinfunction "2_2") (pintype "passive"))
      (node (ref "SV2") (pin "9") (pinfunction "9_9") (pintype "passive"))
    )
    (net (code "80") (name "Net-(R24-Pad2)") (class "Default")
      (node (ref "R24") (pin "2") (pinfunction "2_2") (pintype "passive"))
      (node (ref "SV2") (pin "2") (pinfunction "2_2") (pintype "passive"))
    )
    (net (code "81") (name "Net-(R38-Pad2)") (class "Default")
      (node (ref "R38") (pin "2") (pinfunction "2_2") (pintype "passive"))
      (node (ref "SV2") (pin "7") (pinfunction "7_7") (pintype "passive"))
    )
    (net (code "82") (name "Net-(R39-Pad2)") (class "Default")
      (node (ref "R39") (pin "2") (pinfunction "2_2") (pintype "passive"))
      (node (ref "SV2") (pin "6") (pinfunction "6_6") (pintype "passive"))
    )
    (net (code "83") (name "Net-(R40-Pad2)") (class "Default")
      (node (ref "R40") (pin "2") (pinfunction "2_2") (pintype "passive"))
      (node (ref "SV2") (pin "1") (pinfunction "1_1") (pintype "passive"))
    )
    (net (code "84") (name "Net-(R41-Pad2)") (class "Default")
      (node (ref "R41") (pin "2") (pinfunction "2_2") (pintype "passive"))
      (node (ref "SV2") (pin "3") (pinfunction "3_3") (pintype "passive"))
    )
    (net (code "85") (name "RESET") (class "Default")
      (node (ref "C15") (pin "1") (pinfunction "1_1") (pintype "passive"))
      (node (ref "IC4") (pin "7") (pinfunction "NRST_7") (pintype "bidirectional"))
      (node (ref "JP6") (pin "4") (pinfunction "4_4") (pintype "passive"))
      (node (ref "R4") (pin "2") (pinfunction "2_2") (pintype "passive"))
    )
    (net (code "86") (name "RX") (class "Default")
      (node (ref "IC4") (pin "46") (pinfunction "PB9/SPI2_NSS/I2S2_WS/I2C1_SDA/USART3_RX/CAN_TX/TIM4_CH4_46") (pintype "bidirectional"))
      (node (ref "R9") (pin "2") (pinfunction "2_2") (pintype "passive"))
    )
    (net (code "87") (name "SWCLK") (class "Default")
      (node (ref "IC4") (pin "37") (pinfunction "PA14/I2C1_SDA/JTCK-SWCLK_37") (pintype "bidirectional"))
      (node (ref "JP6") (pin "3") (pinfunction "3_3") (pintype "passive"))
    )
    (net (code "88") (name "SWDIO") (class "Default")
      (node (ref "IC4") (pin "34") (pinfunction "PA13/SPI1_MISO/I2S1_MCK/USART3_CTS/TIM4_CH3/TIM5_CH4/JTMS-SWDIO_34") (pintype "bidirectional"))
      (node (ref "JP6") (pin "2") (pinfunction "2_2") (pintype "passive"))
    )
    (net (code "89") (name "SW_1") (class "Default")
      (node (ref "IC4") (pin "43") (pinfunction "PB7/I2C1_SDA/USART1_RX/TIM4_CH2_43") (pintype "bidirectional"))
      (node (ref "SW1") (pin "3") (pinfunction "3_3") (pintype "passive"))
      (node (ref "SW1") (pin "4") (pinfunction "4_4") (pintype "passive"))
    )
    (net (code "90") (name "SW_2") (class "Default")
      (node (ref "IC4") (pin "42") (pinfunction "PB6/I2C1_SCL/USART1_TX/TIM4_CH1_42") (pintype "bidirectional"))
      (node (ref "SW2") (pin "3") (pinfunction "3_3") (pintype "passive"))
      (node (ref "SW2") (pin "4") (pinfunction "4_4") (pintype "passive"))
    )
    (net (code "91") (name "TIMBRE_ATT") (class "Default")
      (node (ref "C53") (pin "1") (pinfunction "1_1") (pintype "passive"))
      (node (ref "IC4") (pin "16") (pinfunction "PA6/SPI1_MISO/I2S1_MCK/TIM3_CH1/ADC_IN6/DAC2_OUT1_16") (pintype "bidirectional"))
      (node (ref "R42") (pin "P$2") (pinfunction "S_P$2") (pintype "passive"))
    )
    (net (code "92") (name "TIMBRE_POT") (class "Default")
      (node (ref "C32") (pin "1") (pinfunction "1_1") (pintype "passive"))
      (node (ref "IC4") (pin "13") (pinfunction "PA3/SPI3_MOSI/I2S3_SD/USART2_RX/TIM2_CH4/TIM5_CH4/ADC_IN3_13") (pintype "bidirectional"))
      (node (ref "R7") (pin "P$2") (pinfunction "S_P$2") (pintype "passive"))
    )
    (net (code "93") (name "TX") (class "Default")
      (node (ref "IC4") (pin "45") (pinfunction "PB8/SPI2_SCK/I2S2_CK/I2C1_SCL/USART3_TX/CAN_RX/TIM4_CH3_45") (pintype "bidirectional"))
      (node (ref "R10") (pin "2") (pinfunction "2_2") (pintype "passive"))
    )
    (net (code "94") (name "VCC") (class "Default")
      (node (ref "C37") (pin "1") (pinfunction "1_1") (pintype "passive"))
      (node (ref "C4") (pin "+") (pinfunction "+_+") (pintype "passive"))
      (node (ref "IC8") (pin "8") (pinfunction "V+_8") (pintype "power_in"))
      (node (ref "L2") (pin "1") (pinfunction "1_1") (pintype "passive"))
    )
    (net (code "95") (name "VEE") (class "Default")
      (node (ref "C45") (pin "2") (pinfunction "2_2") (pintype "passive"))
      (node (ref "C5") (pin "-") (pinfunction "-_-") (pintype "passive"))
      (node (ref "IC8") (pin "4") (pinfunction "V-_4") (pintype "power_in"))
      (node (ref "L3") (pin "1") (pinfunction "1_1") (pintype "passive"))
      (node (ref "R37") (pin "1") (pinfunction "1_1") (pintype "passive"))
    )
    (net (code "96") (name "unconnected-(IC2-SOUT-Pad22)") (class "Default")
      (node (ref "IC2") (pin "22") (pinfunction "SOUT_22") (pintype "bidirectional"))
    )
    (net (code "97") (name "unconnected-(IC4-PA15{slash}SPI1_NSS{slash}I2S1_WS{slash}SPI3_NSS{slash}I2S3_WS{slash}I2C1_SCL{slash}TIM2_CH1_ETR{slash}JTDI-Pad38)") (class "Default")
      (node (ref "IC4") (pin "38") (pinfunction "PA15/SPI1_NSS/I2S1_WS/SPI3_NSS/I2S3_WS/I2C1_SCL/TIM2_CH1_ETR/JTDI_38") (pintype "bidirectional"))
    )
    (net (code "98") (name "unconnected-(IC4-PB3{slash}SPI1_SCK{slash}I2S1_CK{slash}SPI3_SCK{slash}I2S3_CK{slash}USART2_TX{slash}TIM2_CH2{slash}JTDO{slash}SPI3_SCK{slash}JTDO-Pad39)") (class "Default")
      (node (ref "IC4") (pin "39") (pinfunction "PB3/SPI1_SCK/I2S1_CK/SPI3_SCK/I2S3_CK/USART2_TX/TIM2_CH2/JTDO/SPI3_SCK/JTDO_39") (pintype "bidirectional"))
    )
    (net (code "99") (name "unconnected-(IC4-PB4{slash}SPI1_MISO{slash}I2S1_MCK{slash}SPI3_MISO{slash}I2S3_MCK{slash}USART2_RX{slash}TIM3_CH1{slash}NJTRST-Pad40)") (class "Default")
      (node (ref "IC4") (pin "40") (pinfunction "PB4/SPI1_MISO/I2S1_MCK/SPI3_MISO/I2S3_MCK/USART2_RX/TIM3_CH1/NJTRST_40") (pintype "bidirectional"))
    )
    (net (code "100") (name "unconnected-(IC4-PB5{slash}SPI1_MOSI{slash}I2S1_SD{slash}SPI3_MOSI{slash}I2S3_SD{slash}I2C1_SMBAI{slash}USART2_CK{slash}TIM3_CH2-Pad41)") (class "Default")
      (node (ref "IC4") (pin "41") (pinfunction "PB5/SPI1_MOSI/I2S1_SD/SPI3_MOSI/I2S3_SD/I2C1_SMBAI/USART2_CK/TIM3_CH2_41") (pintype "bidirectional"))
    )
    (net (code "101") (name "unconnected-(IC4-PC13{slash}TIMESTAMP{slash}RTC_TAMPER1-Pad2)") (class "Default")
      (node (ref "IC4") (pin "2") (pinfunction "PC13/TIMESTAMP/RTC_TAMPER1_2") (pintype "bidirectional"))
    )
    (net (code "102") (name "unconnected-(IC4-PC14{slash}OSC32_IN-Pad3)") (class "Default")
      (node (ref "IC4") (pin "3") (pinfunction "PC14/OSC32_IN_3") (pintype "bidirectional"))
    )
    (net (code "103") (name "unconnected-(IC4-PC15{slash}OSC32_OUT-Pad4)") (class "Default")
      (node (ref "IC4") (pin "4") (pinfunction "PC15/OSC32_OUT_4") (pintype "bidirectional"))
    )
    (net (code "104") (name "unconnected-(J11-Pad3)") (class "Default")
      (node (ref "J11") (pin "3") (pinfunction "3_3") (pintype "passive"))
    )
    (net (code "105") (name "unconnected-(J11-Pad6)") (class "Default")
      (node (ref "J11") (pin "6") (pinfunction "6_6") (pintype "passive"))
    )
  )
)
